# tetrad.net
KiCad netlist of a schematic drawn in EAGLE
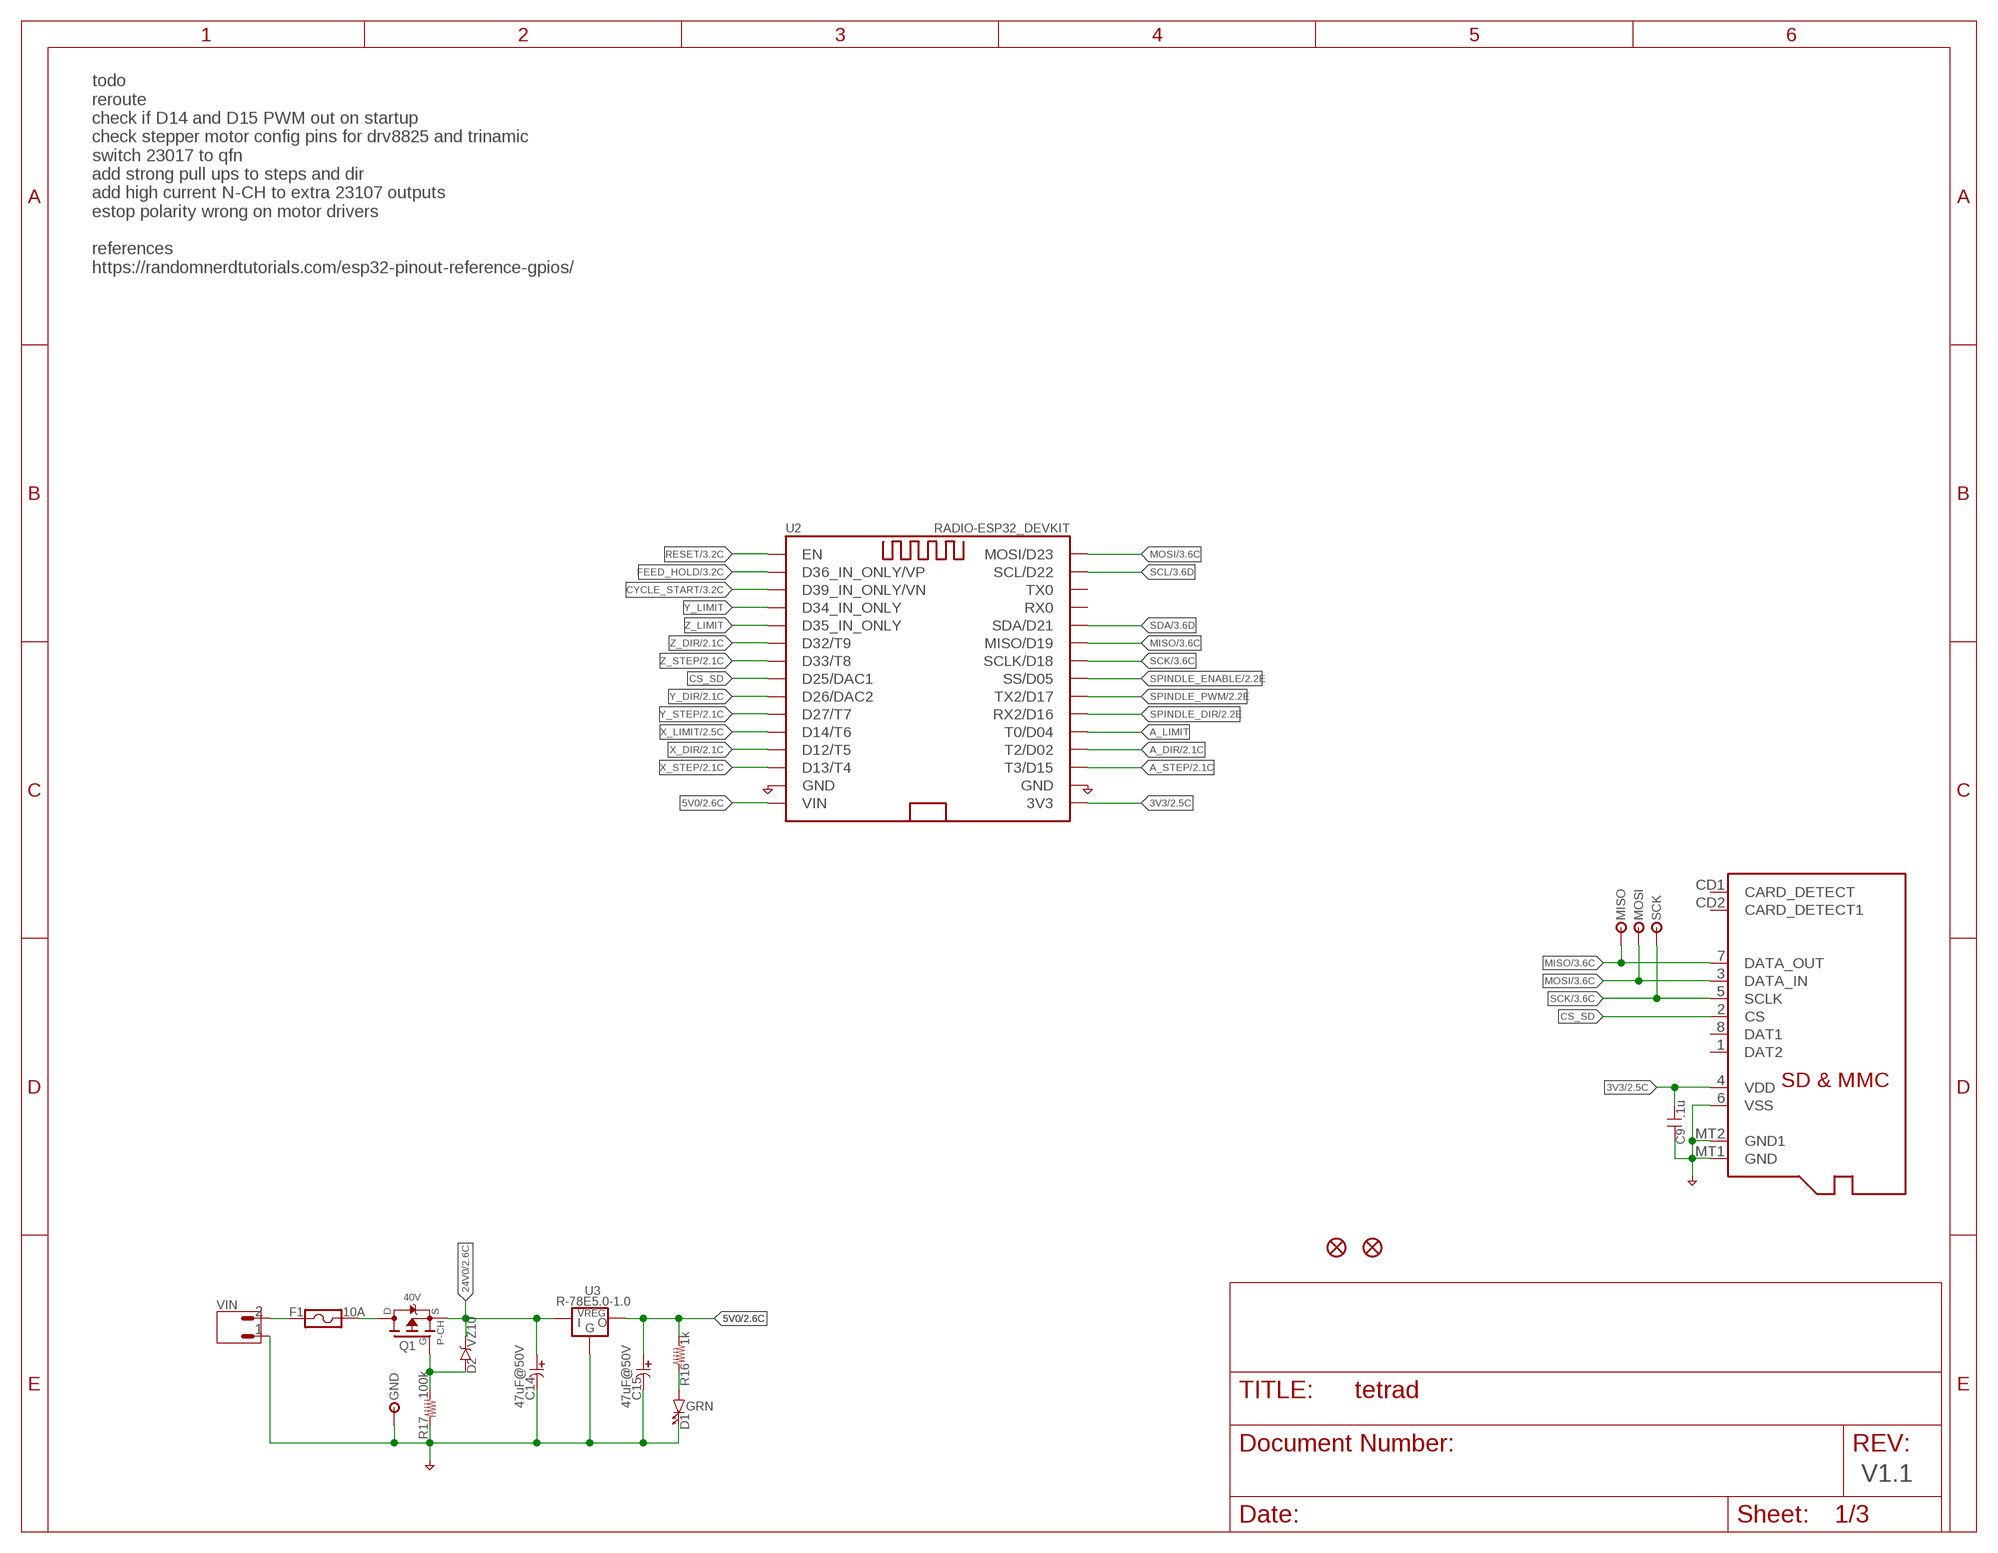
[diagram p0: schematic, sheet 1]
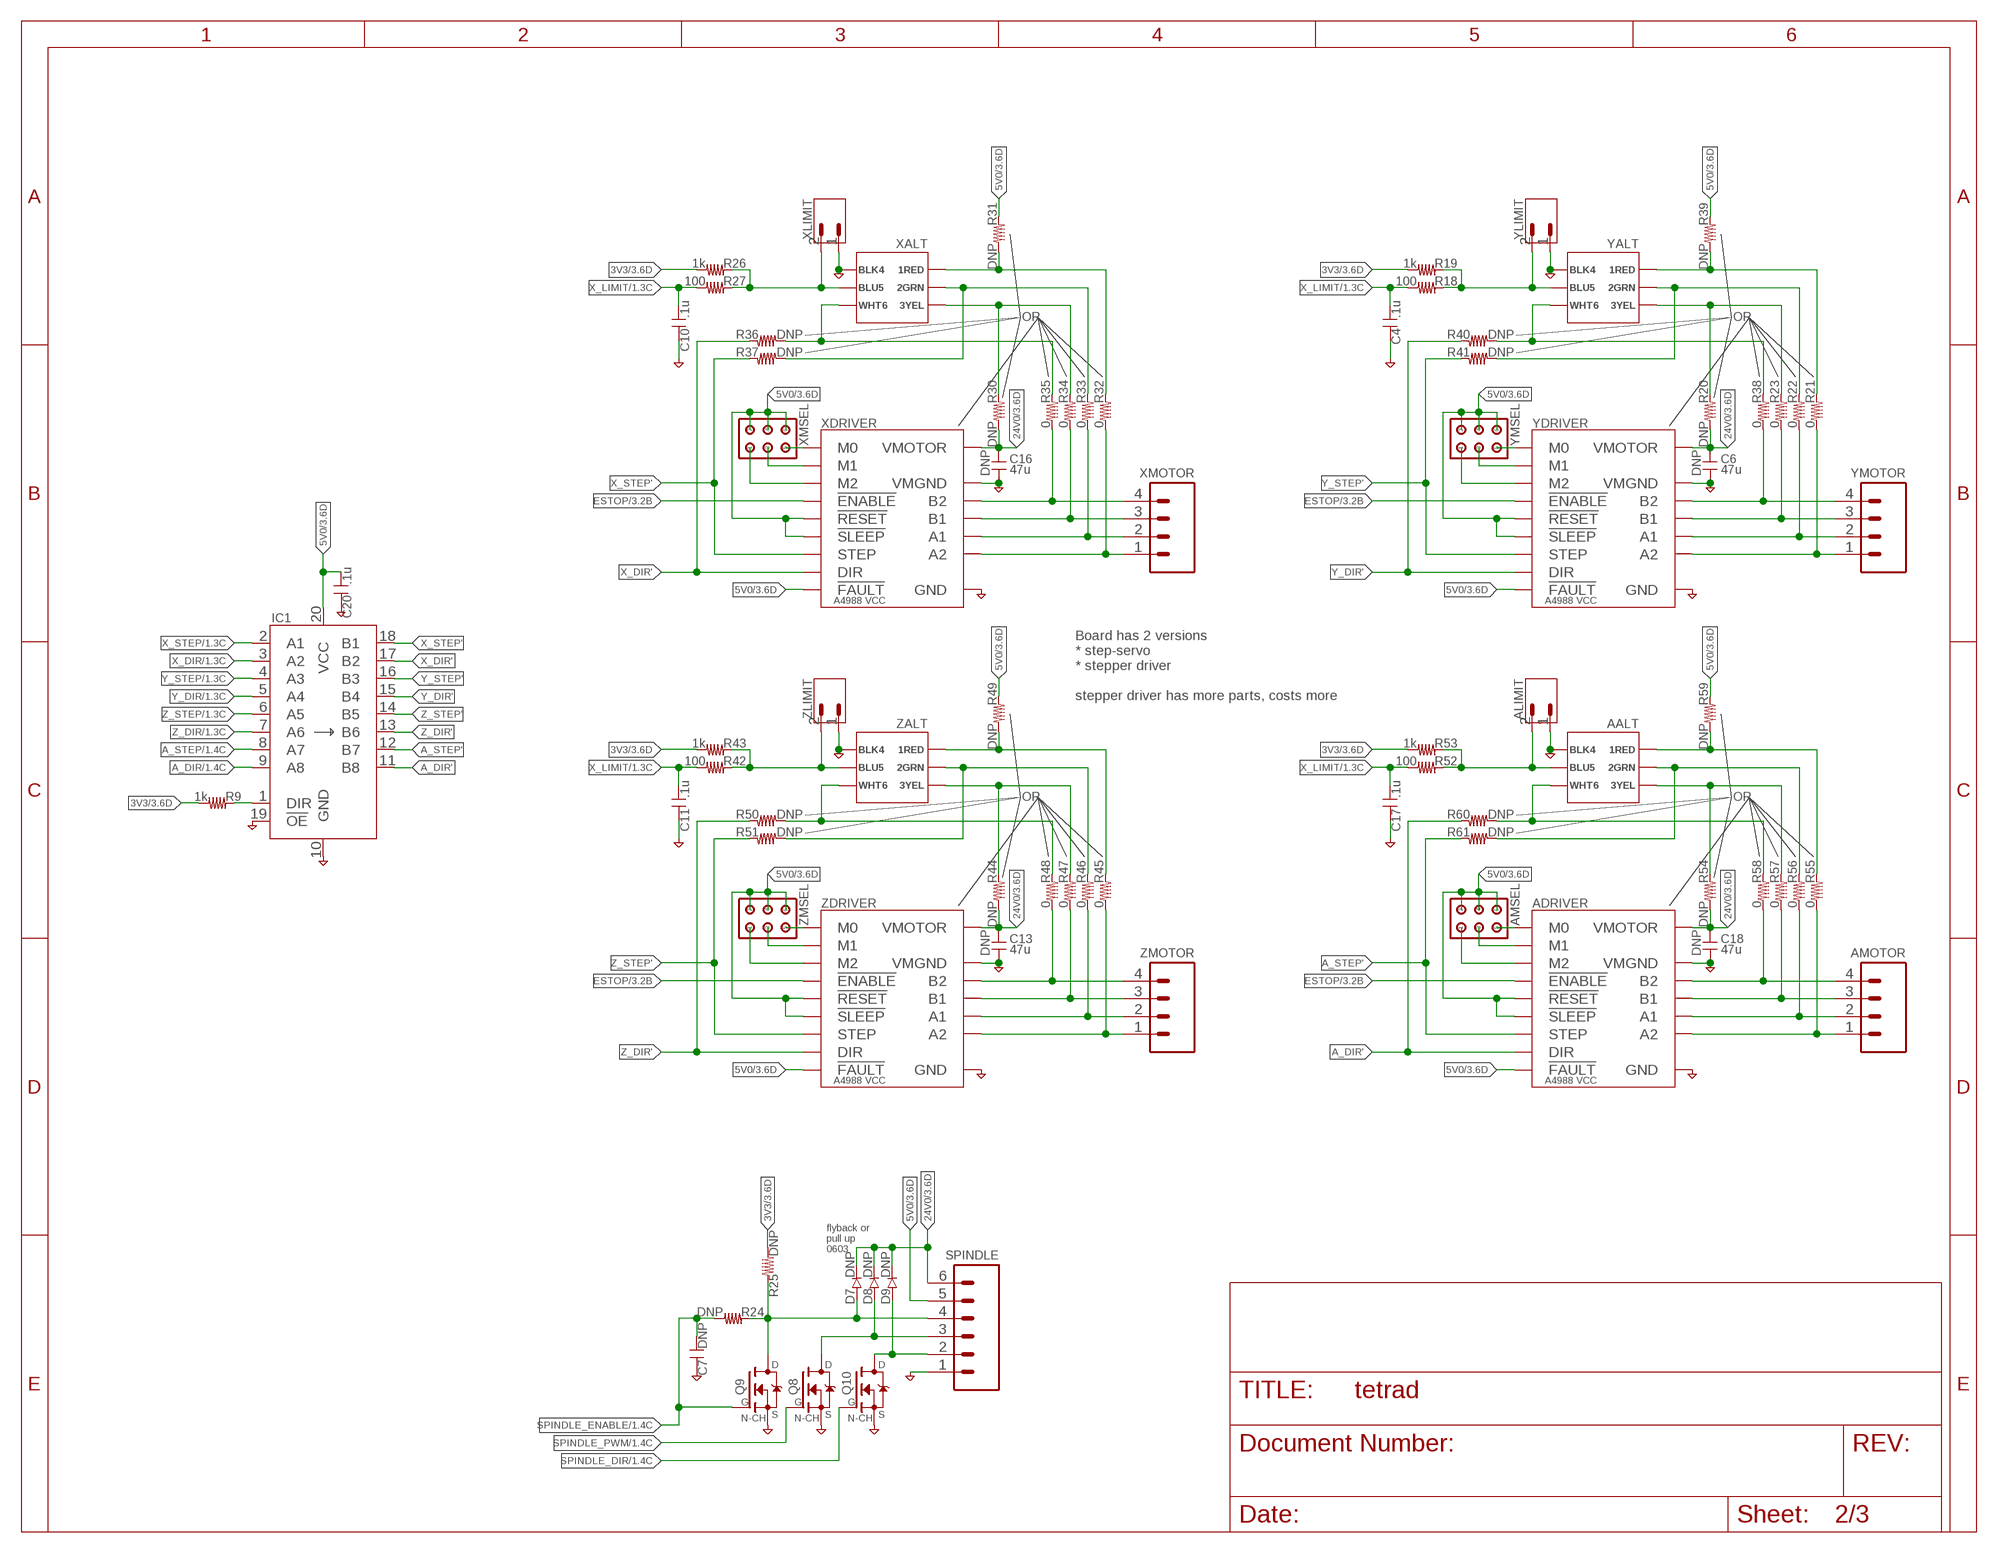
[diagram p1: schematic, sheet 2]
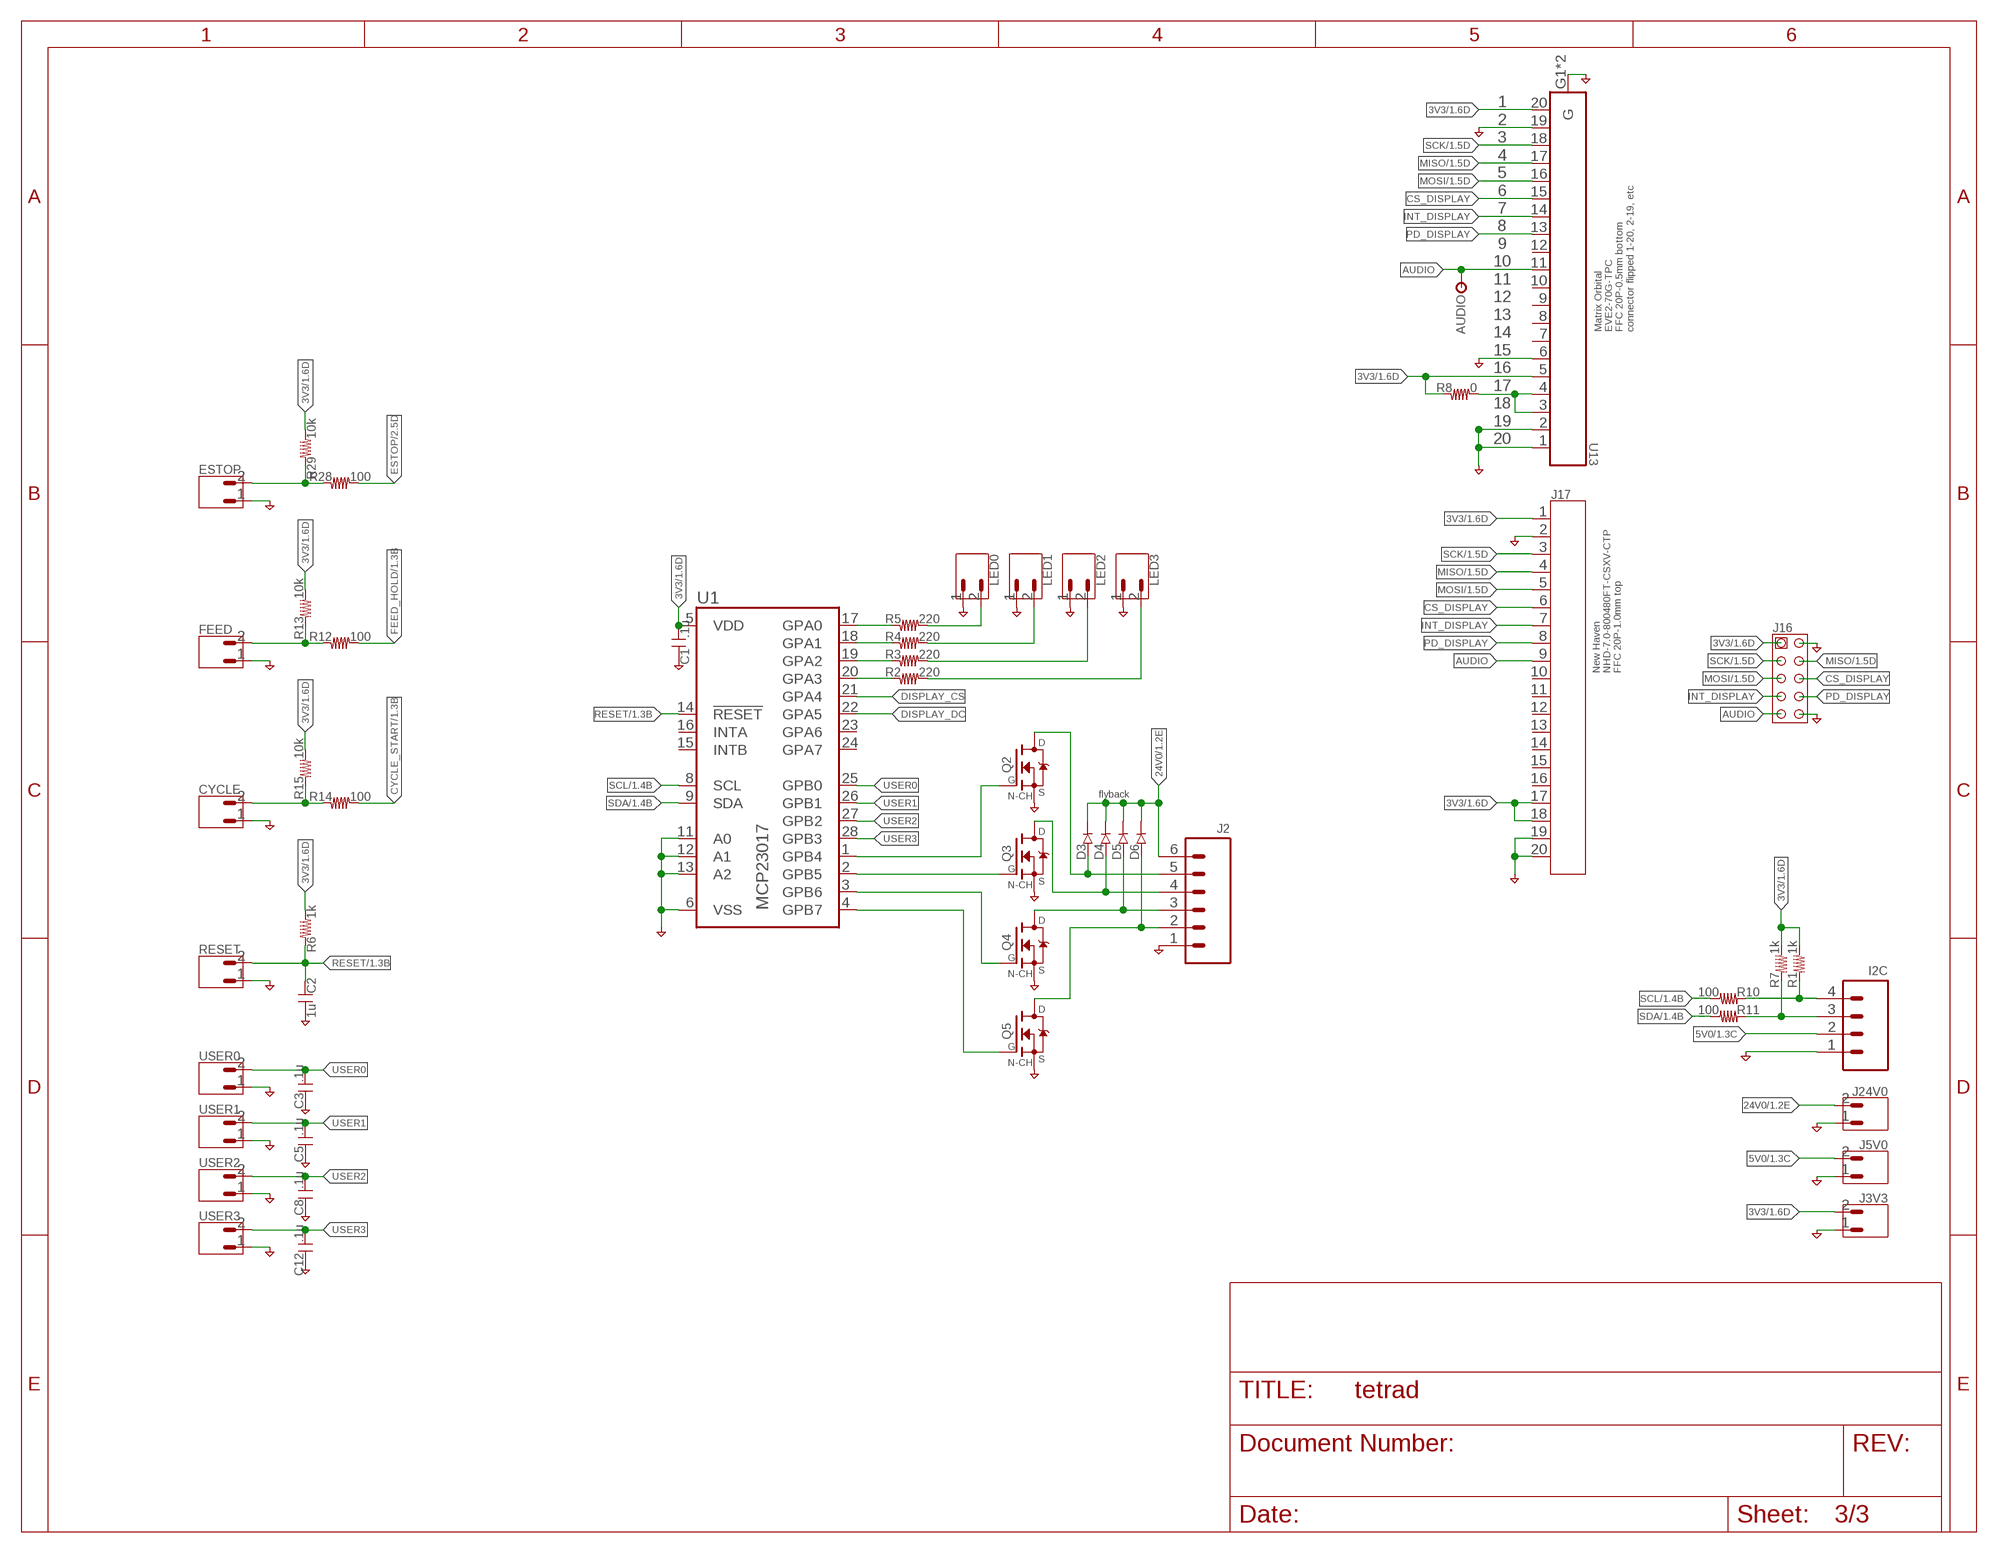
[diagram p2: schematic, sheet 3]

(export (version "E")
  (design (tool "Eeschema 10.0.6"))
  (components
    (comp (ref "AUDIO")
      (value "TESTPOINTTHRU")
      (footprint "eagle-import:TPTHRU")
      (libsource (lib "eagle-import") (part "TESTPOINTTHRU"))
    )
    (comp (ref "C1")
      (value ".1u")
      (footprint "eagle-import:C-0603")
      (libsource (lib "eagle-import") (part "C-0603"))
    )
    (comp (ref "C2")
      (value "1u")
      (footprint "eagle-import:C-0603")
      (libsource (lib "eagle-import") (part "C-0603"))
    )
    (comp (ref "C3")
      (value ".1u")
      (footprint "eagle-import:C-0603")
      (libsource (lib "eagle-import") (part "C-0603"))
    )
    (comp (ref "C5")
      (value ".1u")
      (footprint "eagle-import:C-0603")
      (libsource (lib "eagle-import") (part "C-0603"))
    )
    (comp (ref "C8")
      (value ".1u")
      (footprint "eagle-import:C-0603")
      (libsource (lib "eagle-import") (part "C-0603"))
    )
    (comp (ref "C12")
      (value ".1u")
      (footprint "eagle-import:C-0603")
      (libsource (lib "eagle-import") (part "C-0603"))
    )
    (comp (ref "CYCLE")
      (value "CONN-02-.100-VERT-HEADER")
      (footprint "eagle-import:CONN-.100-2")
      (libsource (lib "eagle-import") (part "CONN-02-.100-VERT-HEADER"))
    )
    (comp (ref "D3")
      (value "DIODE-0603-SOD523")
      (footprint "eagle-import:D-SOD523")
      (libsource (lib "eagle-import") (part "DIODE-0603-SOD523"))
    )
    (comp (ref "D4")
      (value "DIODE-0603-SOD523")
      (footprint "eagle-import:D-SOD523")
      (libsource (lib "eagle-import") (part "DIODE-0603-SOD523"))
    )
    (comp (ref "D5")
      (value "DIODE-0603-SOD523")
      (footprint "eagle-import:D-SOD523")
      (libsource (lib "eagle-import") (part "DIODE-0603-SOD523"))
    )
    (comp (ref "D6")
      (value "DIODE-0603-SOD523")
      (footprint "eagle-import:D-SOD523")
      (libsource (lib "eagle-import") (part "DIODE-0603-SOD523"))
    )
    (comp (ref "ESTOP")
      (value "CONN-02-.100-VERT-HEADER")
      (footprint "eagle-import:CONN-.100-2")
      (libsource (lib "eagle-import") (part "CONN-02-.100-VERT-HEADER"))
    )
    (comp (ref "FEED")
      (value "CONN-02-.100-VERT-HEADER")
      (footprint "eagle-import:CONN-.100-2")
      (libsource (lib "eagle-import") (part "CONN-02-.100-VERT-HEADER"))
    )
    (comp (ref "I2C")
      (value "CONN-04-.100-VERT-HEADER")
      (footprint "eagle-import:CONN-.100-4")
      (libsource (lib "eagle-import") (part "CONN-04-.100-VERT-HEADER"))
    )
    (comp (ref "J2")
      (value "CONN-06-3.81MM-PLUGIN-SCREW")
      (footprint "eagle-import:CONN-3.81MM-KF2EDG-6")
      (libsource (lib "eagle-import") (part "CONN-06-3.81MM-PLUGIN-SCREW"))
    )
    (comp (ref "J3V3")
      (value "CONN-02-.100-VERT-HEADER")
      (footprint "eagle-import:CONN-.100-2")
      (libsource (lib "eagle-import") (part "CONN-02-.100-VERT-HEADER"))
    )
    (comp (ref "J5V0")
      (value "CONN-02-.100-VERT-HEADER")
      (footprint "eagle-import:CONN-.100-2")
      (libsource (lib "eagle-import") (part "CONN-02-.100-VERT-HEADER"))
    )
    (comp (ref "J16")
      (value "CONN-05X2-SHD")
      (footprint "eagle-import:2X5-SHROUDED")
      (libsource (lib "eagle-import") (part "CONN-05X2-SHD"))
    )
    (comp (ref "J17")
      (value "CONN-20-2-84952-0")
      (footprint "eagle-import:CON20_SMT-RA_FCC-FPC2")
      (fields (field (name "MANUFACTURER_PART_NUMBER") "2849520"))
      (libsource (lib "eagle-import") (part "CONN-20-2-84952-0"))
    )
    (comp (ref "J24V0")
      (value "CONN-02-.100-VERT-HEADER")
      (footprint "eagle-import:CONN-.100-2")
      (libsource (lib "eagle-import") (part "CONN-02-.100-VERT-HEADER"))
    )
    (comp (ref "LED0")
      (value "CONN-02-.100-VERT-HEADER")
      (footprint "eagle-import:CONN-.100-2")
      (libsource (lib "eagle-import") (part "CONN-02-.100-VERT-HEADER"))
    )
    (comp (ref "LED1")
      (value "CONN-02-.100-VERT-HEADER")
      (footprint "eagle-import:CONN-.100-2")
      (libsource (lib "eagle-import") (part "CONN-02-.100-VERT-HEADER"))
    )
    (comp (ref "LED2")
      (value "CONN-02-.100-VERT-HEADER")
      (footprint "eagle-import:CONN-.100-2")
      (libsource (lib "eagle-import") (part "CONN-02-.100-VERT-HEADER"))
    )
    (comp (ref "LED3")
      (value "CONN-02-.100-VERT-HEADER")
      (footprint "eagle-import:CONN-.100-2")
      (libsource (lib "eagle-import") (part "CONN-02-.100-VERT-HEADER"))
    )
    (comp (ref "Q2")
      (value "FET-NCH-TO252")
      (footprint "eagle-import:TO252")
      (libsource (lib "eagle-import") (part "FET-NCH-TO252"))
    )
    (comp (ref "Q3")
      (value "FET-NCH-TO252")
      (footprint "eagle-import:TO252")
      (libsource (lib "eagle-import") (part "FET-NCH-TO252"))
    )
    (comp (ref "Q4")
      (value "FET-NCH-TO252")
      (footprint "eagle-import:TO252")
      (libsource (lib "eagle-import") (part "FET-NCH-TO252"))
    )
    (comp (ref "Q5")
      (value "FET-NCH-TO252")
      (footprint "eagle-import:TO252")
      (libsource (lib "eagle-import") (part "FET-NCH-TO252"))
    )
    (comp (ref "R1")
      (value "1k")
      (footprint "eagle-import:R-0603")
      (libsource (lib "eagle-import") (part "R-0603"))
    )
    (comp (ref "R2")
      (value "220")
      (footprint "eagle-import:R-0603")
      (libsource (lib "eagle-import") (part "R-0603"))
    )
    (comp (ref "R3")
      (value "220")
      (footprint "eagle-import:R-0603")
      (libsource (lib "eagle-import") (part "R-0603"))
    )
    (comp (ref "R4")
      (value "220")
      (footprint "eagle-import:R-0603")
      (libsource (lib "eagle-import") (part "R-0603"))
    )
    (comp (ref "R5")
      (value "220")
      (footprint "eagle-import:R-0603")
      (libsource (lib "eagle-import") (part "R-0603"))
    )
    (comp (ref "R6")
      (value "1k")
      (footprint "eagle-import:R-0603")
      (libsource (lib "eagle-import") (part "R-0603"))
    )
    (comp (ref "R7")
      (value "1k")
      (footprint "eagle-import:R-0603")
      (libsource (lib "eagle-import") (part "R-0603"))
    )
    (comp (ref "R8")
      (value "0")
      (footprint "eagle-import:R-0603")
      (libsource (lib "eagle-import") (part "R-0603"))
    )
    (comp (ref "R10")
      (value "100")
      (footprint "eagle-import:R-0603")
      (libsource (lib "eagle-import") (part "R-0603"))
    )
    (comp (ref "R11")
      (value "100")
      (footprint "eagle-import:R-0603")
      (libsource (lib "eagle-import") (part "R-0603"))
    )
    (comp (ref "R12")
      (value "100")
      (footprint "eagle-import:R-0603")
      (libsource (lib "eagle-import") (part "R-0603"))
    )
    (comp (ref "R13")
      (value "10k")
      (footprint "eagle-import:R-0603")
      (libsource (lib "eagle-import") (part "R-0603"))
    )
    (comp (ref "R14")
      (value "100")
      (footprint "eagle-import:R-0603")
      (libsource (lib "eagle-import") (part "R-0603"))
    )
    (comp (ref "R15")
      (value "10k")
      (footprint "eagle-import:R-0603")
      (libsource (lib "eagle-import") (part "R-0603"))
    )
    (comp (ref "R28")
      (value "100")
      (footprint "eagle-import:R-0603")
      (libsource (lib "eagle-import") (part "R-0603"))
    )
    (comp (ref "R29")
      (value "10k")
      (footprint "eagle-import:R-0603")
      (libsource (lib "eagle-import") (part "R-0603"))
    )
    (comp (ref "RESET")
      (value "CONN-02-.100-VERT-HEADER")
      (footprint "eagle-import:CONN-.100-2")
      (libsource (lib "eagle-import") (part "CONN-02-.100-VERT-HEADER"))
    )
    (comp (ref "U1")
      (value "IO-MCP23017ML")
      (footprint "eagle-import:QFN28-ML_6X6MM")
      (fields (field (name "MF") "MICROCHIP") (field (name "MPN") "MCP23017-E/ML"))
      (libsource (lib "eagle-import") (part "IO-MCP23017ML"))
    )
    (comp (ref "U13")
      (value "CONN-20-FPC-0.50MM-10051922-2010ELF")
      (footprint "eagle-import:FCI_10051922-2010ELF")
      (fields (field (name "MF") "Amphenol ICC") (field (name "MP") "10051922-2010ELF"))
      (libsource (lib "eagle-import") (part "CONN-20-FPC-0.50MM-10051922-2010ELF"))
    )
    (comp (ref "USER0")
      (value "CONN-02-.100-VERT-HEADER")
      (footprint "eagle-import:CONN-.100-2")
      (libsource (lib "eagle-import") (part "CONN-02-.100-VERT-HEADER"))
    )
    (comp (ref "USER1")
      (value "CONN-02-.100-VERT-HEADER")
      (footprint "eagle-import:CONN-.100-2")
      (libsource (lib "eagle-import") (part "CONN-02-.100-VERT-HEADER"))
    )
    (comp (ref "USER2")
      (value "CONN-02-.100-VERT-HEADER")
      (footprint "eagle-import:CONN-.100-2")
      (libsource (lib "eagle-import") (part "CONN-02-.100-VERT-HEADER"))
    )
    (comp (ref "USER3")
      (value "CONN-02-.100-VERT-HEADER")
      (footprint "eagle-import:CONN-.100-2")
      (libsource (lib "eagle-import") (part "CONN-02-.100-VERT-HEADER"))
    )
    (comp (ref "AALT")
      (value "CONN-03X2-MICROFIT-TH-SMD")
      (footprint "eagle-import:MOLEX_430450614_430450615")
      (libsource (lib "eagle-import") (part "CONN-03X2-MICROFIT-TH-SMD"))
    )
    (comp (ref "ADRIVER")
      (value "BOARD-DRV8825-CARRIER-TH-SMD")
      (footprint "eagle-import:IC_DRV8825_CARRIER_TH_SMD")
      (fields (field (name "MF") "Pololu") (field (name "MP") "DRV8825 STEPPER MOTOR DRIVER CARRIER"))
      (libsource (lib "eagle-import") (part "BOARD-DRV8825-CARRIER-TH-SMD"))
    )
    (comp (ref "ALIMIT")
      (value "CONN-02-.100-VERT-HEADER")
      (footprint "eagle-import:CONN-.100-2")
      (libsource (lib "eagle-import") (part "CONN-02-.100-VERT-HEADER"))
    )
    (comp (ref "AMOTOR")
      (value "CONN-04-.100-VERT-HEADER")
      (footprint "eagle-import:CONN-.100-4")
      (libsource (lib "eagle-import") (part "CONN-04-.100-VERT-HEADER"))
    )
    (comp (ref "AMSEL")
      (value "CONN-03X2-RH")
      (footprint "eagle-import:AMPHENOL_95278-101A06LF")
      (libsource (lib "eagle-import") (part "CONN-03X2-RH"))
    )
    (comp (ref "C4")
      (value ".1u")
      (footprint "eagle-import:C-0603")
      (libsource (lib "eagle-import") (part "C-0603"))
    )
    (comp (ref "C6")
      (value "DNP")
      (footprint "eagle-import:C-1206")
      (libsource (lib "eagle-import") (part "C-1206"))
    )
    (comp (ref "C7")
      (value "DNP")
      (footprint "eagle-import:C-0603")
      (libsource (lib "eagle-import") (part "C-0603"))
    )
    (comp (ref "C10")
      (value ".1u")
      (footprint "eagle-import:C-0603")
      (libsource (lib "eagle-import") (part "C-0603"))
    )
    (comp (ref "C11")
      (value ".1u")
      (footprint "eagle-import:C-0603")
      (libsource (lib "eagle-import") (part "C-0603"))
    )
    (comp (ref "C13")
      (value "DNP")
      (footprint "eagle-import:C-1206")
      (libsource (lib "eagle-import") (part "C-1206"))
    )
    (comp (ref "C16")
      (value "DNP")
      (footprint "eagle-import:C-1206")
      (libsource (lib "eagle-import") (part "C-1206"))
    )
    (comp (ref "C17")
      (value ".1u")
      (footprint "eagle-import:C-0603")
      (libsource (lib "eagle-import") (part "C-0603"))
    )
    (comp (ref "C18")
      (value "DNP")
      (footprint "eagle-import:C-1206")
      (libsource (lib "eagle-import") (part "C-1206"))
    )
    (comp (ref "C20")
      (value ".1u")
      (footprint "eagle-import:C-0603")
      (libsource (lib "eagle-import") (part "C-0603"))
    )
    (comp (ref "D7")
      (value "DNP")
      (footprint "eagle-import:D-SOD523")
      (libsource (lib "eagle-import") (part "DIODE-0603-SOD523"))
    )
    (comp (ref "D8")
      (value "DNP")
      (footprint "eagle-import:D-SOD523")
      (libsource (lib "eagle-import") (part "DIODE-0603-SOD523"))
    )
    (comp (ref "D9")
      (value "DNP")
      (footprint "eagle-import:D-SOD523")
      (libsource (lib "eagle-import") (part "DIODE-0603-SOD523"))
    )
    (comp (ref "IC1")
      (value "74LS245DW")
      (footprint "eagle-import:SO20W")
      (libsource (lib "eagle-import") (part "74245DWLS"))
    )
    (comp (ref "Q8")
      (value "FET-NCH-SOT23")
      (footprint "eagle-import:SOT23-3")
      (libsource (lib "eagle-import") (part "FET-NCH-SOT23"))
    )
    (comp (ref "Q9")
      (value "FET-NCH-SOT23")
      (footprint "eagle-import:SOT23-3")
      (libsource (lib "eagle-import") (part "FET-NCH-SOT23"))
    )
    (comp (ref "Q10")
      (value "FET-NCH-SOT23")
      (footprint "eagle-import:SOT23-3")
      (libsource (lib "eagle-import") (part "FET-NCH-SOT23"))
    )
    (comp (ref "R9")
      (value "1k")
      (footprint "eagle-import:R-0603")
      (libsource (lib "eagle-import") (part "R-0603"))
    )
    (comp (ref "R18")
      (value "100")
      (footprint "eagle-import:R-0603")
      (libsource (lib "eagle-import") (part "R-0603"))
    )
    (comp (ref "R19")
      (value "1k")
      (footprint "eagle-import:R-0603")
      (libsource (lib "eagle-import") (part "R-0603"))
    )
    (comp (ref "R20")
      (value "DNP")
      (footprint "eagle-import:R-0603")
      (libsource (lib "eagle-import") (part "R-0603"))
    )
    (comp (ref "R21")
      (value "0")
      (footprint "eagle-import:R-0603")
      (libsource (lib "eagle-import") (part "R-0603"))
    )
    (comp (ref "R22")
      (value "0")
      (footprint "eagle-import:R-0603")
      (libsource (lib "eagle-import") (part "R-0603"))
    )
    (comp (ref "R23")
      (value "0")
      (footprint "eagle-import:R-0603")
      (libsource (lib "eagle-import") (part "R-0603"))
    )
    (comp (ref "R24")
      (value "DNP")
      (footprint "eagle-import:R-0603")
      (libsource (lib "eagle-import") (part "R-0603"))
    )
    (comp (ref "R25")
      (value "DNP")
      (footprint "eagle-import:R-0603")
      (libsource (lib "eagle-import") (part "R-0603"))
    )
    (comp (ref "R26")
      (value "1k")
      (footprint "eagle-import:R-0603")
      (libsource (lib "eagle-import") (part "R-0603"))
    )
    (comp (ref "R27")
      (value "100")
      (footprint "eagle-import:R-0603")
      (libsource (lib "eagle-import") (part "R-0603"))
    )
    (comp (ref "R30")
      (value "DNP")
      (footprint "eagle-import:R-0603")
      (libsource (lib "eagle-import") (part "R-0603"))
    )
    (comp (ref "R31")
      (value "DNP")
      (footprint "eagle-import:R-0603")
      (libsource (lib "eagle-import") (part "R-0603"))
    )
    (comp (ref "R32")
      (value "0")
      (footprint "eagle-import:R-0603")
      (libsource (lib "eagle-import") (part "R-0603"))
    )
    (comp (ref "R33")
      (value "0")
      (footprint "eagle-import:R-0603")
      (libsource (lib "eagle-import") (part "R-0603"))
    )
    (comp (ref "R34")
      (value "0")
      (footprint "eagle-import:R-0603")
      (libsource (lib "eagle-import") (part "R-0603"))
    )
    (comp (ref "R35")
      (value "0")
      (footprint "eagle-import:R-0603")
      (libsource (lib "eagle-import") (part "R-0603"))
    )
    (comp (ref "R36")
      (value "DNP")
      (footprint "eagle-import:R-0603")
      (libsource (lib "eagle-import") (part "R-0603"))
    )
    (comp (ref "R37")
      (value "DNP")
      (footprint "eagle-import:R-0603")
      (libsource (lib "eagle-import") (part "R-0603"))
    )
    (comp (ref "R38")
      (value "0")
      (footprint "eagle-import:R-0603")
      (libsource (lib "eagle-import") (part "R-0603"))
    )
    (comp (ref "R39")
      (value "DNP")
      (footprint "eagle-import:R-0603")
      (libsource (lib "eagle-import") (part "R-0603"))
    )
    (comp (ref "R40")
      (value "DNP")
      (footprint "eagle-import:R-0603")
      (libsource (lib "eagle-import") (part "R-0603"))
    )
    (comp (ref "R41")
      (value "DNP")
      (footprint "eagle-import:R-0603")
      (libsource (lib "eagle-import") (part "R-0603"))
    )
    (comp (ref "R42")
      (value "100")
      (footprint "eagle-import:R-0603")
      (libsource (lib "eagle-import") (part "R-0603"))
    )
    (comp (ref "R43")
      (value "1k")
      (footprint "eagle-import:R-0603")
      (libsource (lib "eagle-import") (part "R-0603"))
    )
    (comp (ref "R44")
      (value "DNP")
      (footprint "eagle-import:R-0603")
      (libsource (lib "eagle-import") (part "R-0603"))
    )
    (comp (ref "R45")
      (value "0")
      (footprint "eagle-import:R-0603")
      (libsource (lib "eagle-import") (part "R-0603"))
    )
    (comp (ref "R46")
      (value "0")
      (footprint "eagle-import:R-0603")
      (libsource (lib "eagle-import") (part "R-0603"))
    )
    (comp (ref "R47")
      (value "0")
      (footprint "eagle-import:R-0603")
      (libsource (lib "eagle-import") (part "R-0603"))
    )
    (comp (ref "R48")
      (value "0")
      (footprint "eagle-import:R-0603")
      (libsource (lib "eagle-import") (part "R-0603"))
    )
    (comp (ref "R49")
      (value "DNP")
      (footprint "eagle-import:R-0603")
      (libsource (lib "eagle-import") (part "R-0603"))
    )
    (comp (ref "R50")
      (value "DNP")
      (footprint "eagle-import:R-0603")
      (libsource (lib "eagle-import") (part "R-0603"))
    )
    (comp (ref "R51")
      (value "DNP")
      (footprint "eagle-import:R-0603")
      (libsource (lib "eagle-import") (part "R-0603"))
    )
    (comp (ref "R52")
      (value "100")
      (footprint "eagle-import:R-0603")
      (libsource (lib "eagle-import") (part "R-0603"))
    )
    (comp (ref "R53")
      (value "1k")
      (footprint "eagle-import:R-0603")
      (libsource (lib "eagle-import") (part "R-0603"))
    )
    (comp (ref "R54")
      (value "DNP")
      (footprint "eagle-import:R-0603")
      (libsource (lib "eagle-import") (part "R-0603"))
    )
    (comp (ref "R55")
      (value "0")
      (footprint "eagle-import:R-0603")
      (libsource (lib "eagle-import") (part "R-0603"))
    )
    (comp (ref "R56")
      (value "0")
      (footprint "eagle-import:R-0603")
      (libsource (lib "eagle-import") (part "R-0603"))
    )
    (comp (ref "R57")
      (value "0")
      (footprint "eagle-import:R-0603")
      (libsource (lib "eagle-import") (part "R-0603"))
    )
    (comp (ref "R58")
      (value "0")
      (footprint "eagle-import:R-0603")
      (libsource (lib "eagle-import") (part "R-0603"))
    )
    (comp (ref "R59")
      (value "DNP")
      (footprint "eagle-import:R-0603")
      (libsource (lib "eagle-import") (part "R-0603"))
    )
    (comp (ref "R60")
      (value "DNP")
      (footprint "eagle-import:R-0603")
      (libsource (lib "eagle-import") (part "R-0603"))
    )
    (comp (ref "R61")
      (value "DNP")
      (footprint "eagle-import:R-0603")
      (libsource (lib "eagle-import") (part "R-0603"))
    )
    (comp (ref "SPINDLE")
      (value "CONN-06-.100-VERT-HEADER")
      (footprint "eagle-import:CONN-.100-6")
      (libsource (lib "eagle-import") (part "CONN-06-.100-VERT-HEADER"))
    )
    (comp (ref "XALT")
      (value "CONN-03X2-MICROFIT-TH-SMD")
      (footprint "eagle-import:MOLEX_430450614_430450615")
      (libsource (lib "eagle-import") (part "CONN-03X2-MICROFIT-TH-SMD"))
    )
    (comp (ref "XDRIVER")
      (value "BOARD-DRV8825-CARRIER-TH-SMD")
      (footprint "eagle-import:IC_DRV8825_CARRIER_TH_SMD")
      (fields (field (name "MF") "Pololu") (field (name "MP") "DRV8825 STEPPER MOTOR DRIVER CARRIER"))
      (libsource (lib "eagle-import") (part "BOARD-DRV8825-CARRIER-TH-SMD"))
    )
    (comp (ref "XLIMIT")
      (value "CONN-02-.100-VERT-HEADER")
      (footprint "eagle-import:CONN-.100-2")
      (libsource (lib "eagle-import") (part "CONN-02-.100-VERT-HEADER"))
    )
    (comp (ref "XMOTOR")
      (value "CONN-04-.100-VERT-HEADER")
      (footprint "eagle-import:CONN-.100-4")
      (libsource (lib "eagle-import") (part "CONN-04-.100-VERT-HEADER"))
    )
    (comp (ref "XMSEL")
      (value "CONN-03X2-RH")
      (footprint "eagle-import:AMPHENOL_95278-101A06LF")
      (libsource (lib "eagle-import") (part "CONN-03X2-RH"))
    )
    (comp (ref "YALT")
      (value "CONN-03X2-MICROFIT-TH-SMD")
      (footprint "eagle-import:MOLEX_430450614_430450615")
      (libsource (lib "eagle-import") (part "CONN-03X2-MICROFIT-TH-SMD"))
    )
    (comp (ref "YDRIVER")
      (value "BOARD-DRV8825-CARRIER-TH-SMD")
      (footprint "eagle-import:IC_DRV8825_CARRIER_TH_SMD")
      (fields (field (name "MF") "Pololu") (field (name "MP") "DRV8825 STEPPER MOTOR DRIVER CARRIER"))
      (libsource (lib "eagle-import") (part "BOARD-DRV8825-CARRIER-TH-SMD"))
    )
    (comp (ref "YLIMIT")
      (value "CONN-02-.100-VERT-HEADER")
      (footprint "eagle-import:CONN-.100-2")
      (libsource (lib "eagle-import") (part "CONN-02-.100-VERT-HEADER"))
    )
    (comp (ref "YMOTOR")
      (value "CONN-04-.100-VERT-HEADER")
      (footprint "eagle-import:CONN-.100-4")
      (libsource (lib "eagle-import") (part "CONN-04-.100-VERT-HEADER"))
    )
    (comp (ref "YMSEL")
      (value "CONN-03X2-RH")
      (footprint "eagle-import:AMPHENOL_95278-101A06LF")
      (libsource (lib "eagle-import") (part "CONN-03X2-RH"))
    )
    (comp (ref "ZALT")
      (value "CONN-03X2-MICROFIT-TH-SMD")
      (footprint "eagle-import:MOLEX_430450614_430450615")
      (libsource (lib "eagle-import") (part "CONN-03X2-MICROFIT-TH-SMD"))
    )
    (comp (ref "ZDRIVER")
      (value "BOARD-DRV8825-CARRIER-TH-SMD")
      (footprint "eagle-import:IC_DRV8825_CARRIER_TH_SMD")
      (fields (field (name "MF") "Pololu") (field (name "MP") "DRV8825 STEPPER MOTOR DRIVER CARRIER"))
      (libsource (lib "eagle-import") (part "BOARD-DRV8825-CARRIER-TH-SMD"))
    )
    (comp (ref "ZLIMIT")
      (value "CONN-02-.100-VERT-HEADER")
      (footprint "eagle-import:CONN-.100-2")
      (libsource (lib "eagle-import") (part "CONN-02-.100-VERT-HEADER"))
    )
    (comp (ref "ZMOTOR")
      (value "CONN-04-.100-VERT-HEADER")
      (footprint "eagle-import:CONN-.100-4")
      (libsource (lib "eagle-import") (part "CONN-04-.100-VERT-HEADER"))
    )
    (comp (ref "ZMSEL")
      (value "CONN-03X2-RH")
      (footprint "eagle-import:AMPHENOL_95278-101A06LF")
      (libsource (lib "eagle-import") (part "CONN-03X2-RH"))
    )
    (comp (ref "C9")
      (value ".1u")
      (footprint "eagle-import:C-0603")
      (libsource (lib "eagle-import") (part "C-0603"))
    )
    (comp (ref "C14")
      (value "47uF@50V")
      (footprint "eagle-import:C-E-6")
      (libsource (lib "eagle-import") (part "C-POLARIZED-E-6"))
    )
    (comp (ref "C15")
      (value "47uF@50V")
      (footprint "eagle-import:C-E-6")
      (libsource (lib "eagle-import") (part "C-POLARIZED-E-6"))
    )
    (comp (ref "D1")
      (value "GRN")
      (footprint "eagle-import:LED-0603")
      (libsource (lib "eagle-import") (part "LED-0603"))
    )
    (comp (ref "D2")
      (value "VZ10")
      (footprint "eagle-import:D-SOD323")
      (libsource (lib "eagle-import") (part "DIODE-ZENER-SOD323"))
    )
    (comp (ref "F1")
      (value "10A")
      (footprint "eagle-import:3557-2")
      (libsource (lib "eagle-import") (part "FUSE-HOLDER-3557-2"))
    )
    (comp (ref "FID1")
      (value "FIDUCIAL-MICRO")
      (footprint "eagle-import:FIDUCIAL-MICRO")
      (libsource (lib "eagle-import") (part "FIDUCIAL-MICRO"))
    )
    (comp (ref "FID2")
      (value "FIDUCIAL-MICRO")
      (footprint "eagle-import:FIDUCIAL-MICRO")
      (libsource (lib "eagle-import") (part "FIDUCIAL-MICRO"))
    )
    (comp (ref "GND")
      (value "TESTPOINTTHRU")
      (footprint "eagle-import:TPTHRU")
      (libsource (lib "eagle-import") (part "TESTPOINTTHRU"))
    )
    (comp (ref "J1")
      (value "CONN-MICROSD-2908-05WB-MG")
      (footprint "eagle-import:CONN-MICROSD-2908-05WB-MG")
      (libsource (lib "eagle-import") (part "CONN-MICROSD-2908-05WB-MG"))
    )
    (comp (ref "MISO")
      (value "TESTPOINTTHRU")
      (footprint "eagle-import:TPTHRU")
      (libsource (lib "eagle-import") (part "TESTPOINTTHRU"))
    )
    (comp (ref "MOSI")
      (value "TESTPOINTTHRU")
      (footprint "eagle-import:TPTHRU")
      (libsource (lib "eagle-import") (part "TESTPOINTTHRU"))
    )
    (comp (ref "Q1")
      (value "FET-PCH-TO252")
      (footprint "eagle-import:TO252")
      (libsource (lib "eagle-import") (part "FET-PCH-TO252"))
    )
    (comp (ref "R16")
      (value "1k")
      (footprint "eagle-import:R-0603")
      (libsource (lib "eagle-import") (part "R-0603"))
    )
    (comp (ref "R17")
      (value "100k")
      (footprint "eagle-import:R-0603")
      (libsource (lib "eagle-import") (part "R-0603"))
    )
    (comp (ref "SCK")
      (value "TESTPOINTTHRU")
      (footprint "eagle-import:TPTHRU")
      (libsource (lib "eagle-import") (part "TESTPOINTTHRU"))
    )
    (comp (ref "U2")
      (value "RADIO-ESP32_DEVKIT")
      (footprint "eagle-import:ESP32_DEVKIT")
      (libsource (lib "eagle-import") (part "RADIO-ESP32_DEVKIT"))
    )
    (comp (ref "U3")
      (value "R-78E5.0-1.0")
      (footprint "eagle-import:VREG-SIP3")
      (libsource (lib "eagle-import") (part "VREG-SIP3"))
    )
    (comp (ref "VIN")
      (value "CONN-02-3.81MM-PLUGIN-SCREW")
      (footprint "eagle-import:CONN-3.81MM-KF2EDG-2")
      (libsource (lib "eagle-import") (part "CONN-02-3.81MM-PLUGIN-SCREW"))
    )
  )
  (nets
    (net (code "1") (name "3V3") (class "Default")
      (node (ref "C1") (pin "1") (pinfunction "1_1") (pintype "passive"))
      (node (ref "C9") (pin "1") (pinfunction "1_1") (pintype "passive"))
      (node (ref "J1") (pin "4") (pinfunction "VDD_4") (pintype "power_in"))
      (node (ref "J16") (pin "1") (pinfunction "1_1") (pintype "passive"))
      (node (ref "J17") (pin "1") (pinfunction "1_1") (pintype "passive"))
      (node (ref "J17") (pin "17") (pinfunction "17_17") (pintype "passive"))
      (node (ref "J17") (pin "18") (pinfunction "18_18") (pintype "passive"))
      (node (ref "J3V3") (pin "2") (pinfunction "2_2") (pintype "passive"))
      (node (ref "R1") (pin "2") (pinfunction "2_2") (pintype "passive"))
      (node (ref "R13") (pin "2") (pinfunction "2_2") (pintype "passive"))
      (node (ref "R15") (pin "2") (pinfunction "2_2") (pintype "passive"))
      (node (ref "R19") (pin "2") (pinfunction "2_2") (pintype "passive"))
      (node (ref "R25") (pin "2") (pinfunction "2_2") (pintype "passive"))
      (node (ref "R26") (pin "2") (pinfunction "2_2") (pintype "passive"))
      (node (ref "R29") (pin "2") (pinfunction "2_2") (pintype "passive"))
      (node (ref "R43") (pin "2") (pinfunction "2_2") (pintype "passive"))
      (node (ref "R53") (pin "2") (pinfunction "2_2") (pintype "passive"))
      (node (ref "R6") (pin "2") (pinfunction "2_2") (pintype "passive"))
      (node (ref "R7") (pin "2") (pinfunction "2_2") (pintype "passive"))
      (node (ref "R8") (pin "1") (pinfunction "1_1") (pintype "passive"))
      (node (ref "R9") (pin "2") (pinfunction "2_2") (pintype "passive"))
      (node (ref "U1") (pin "5") (pinfunction "VDD_5") (pintype "power_in"))
      (node (ref "U13") (pin "20") (pinfunction "20_20") (pintype "bidirectional"))
      (node (ref "U13") (pin "5") (pinfunction "5_5") (pintype "passive"))
      (node (ref "U2") (pin "3V3") (pinfunction "3V3_3V3") (pintype "bidirectional"))
    )
    (net (code "2") (name "5V0") (class "Default")
      (node (ref "ADRIVER") (pin "10") (pinfunction "~{FAULT}_10") (pintype "output"))
      (node (ref "ADRIVER") (pin "10_") (pinfunction "~{FAULT}_10_") (pintype "output"))
      (node (ref "ADRIVER") (pin "5") (pinfunction "~{RESET}_5") (pintype "input"))
      (node (ref "ADRIVER") (pin "5_") (pinfunction "~{RESET}_5_") (pintype "input"))
      (node (ref "ADRIVER") (pin "6") (pinfunction "~{SLEEP}_6") (pintype "input"))
      (node (ref "ADRIVER") (pin "6_") (pinfunction "~{SLEEP}_6_") (pintype "input"))
      (node (ref "AMSEL") (pin "2") (pinfunction "2_2") (pintype "passive"))
      (node (ref "AMSEL") (pin "4") (pinfunction "4_4") (pintype "passive"))
      (node (ref "AMSEL") (pin "6") (pinfunction "6_6") (pintype "passive"))
      (node (ref "C15") (pin "+") (pinfunction "+_+") (pintype "passive"))
      (node (ref "C20") (pin "1") (pinfunction "1_1") (pintype "passive"))
      (node (ref "I2C") (pin "2") (pinfunction "2_2") (pintype "passive"))
      (node (ref "IC1") (pin "20") (pinfunction "VCC_20") (pintype "bidirectional"))
      (node (ref "J5V0") (pin "2") (pinfunction "2_2") (pintype "passive"))
      (node (ref "R16") (pin "2") (pinfunction "2_2") (pintype "passive"))
      (node (ref "R31") (pin "1") (pinfunction "1_1") (pintype "passive"))
      (node (ref "R39") (pin "1") (pinfunction "1_1") (pintype "passive"))
      (node (ref "R49") (pin "1") (pinfunction "1_1") (pintype "passive"))
      (node (ref "R59") (pin "1") (pinfunction "1_1") (pintype "passive"))
      (node (ref "SPINDLE") (pin "5") (pinfunction "5_5") (pintype "passive"))
      (node (ref "U2") (pin "VIN") (pinfunction "VIN_VIN") (pintype "bidirectional"))
      (node (ref "U3") (pin "3") (pinfunction "VOUT_3") (pintype "bidirectional"))
      (node (ref "XDRIVER") (pin "10") (pinfunction "~{FAULT}_10") (pintype "output"))
      (node (ref "XDRIVER") (pin "10_") (pinfunction "~{FAULT}_10_") (pintype "output"))
      (node (ref "XDRIVER") (pin "5") (pinfunction "~{RESET}_5") (pintype "input"))
      (node (ref "XDRIVER") (pin "5_") (pinfunction "~{RESET}_5_") (pintype "input"))
      (node (ref "XDRIVER") (pin "6") (pinfunction "~{SLEEP}_6") (pintype "input"))
      (node (ref "XDRIVER") (pin "6_") (pinfunction "~{SLEEP}_6_") (pintype "input"))
      (node (ref "XMSEL") (pin "2") (pinfunction "2_2") (pintype "passive"))
      (node (ref "XMSEL") (pin "4") (pinfunction "4_4") (pintype "passive"))
      (node (ref "XMSEL") (pin "6") (pinfunction "6_6") (pintype "passive"))
      (node (ref "YDRIVER") (pin "10") (pinfunction "~{FAULT}_10") (pintype "output"))
      (node (ref "YDRIVER") (pin "10_") (pinfunction "~{FAULT}_10_") (pintype "output"))
      (node (ref "YDRIVER") (pin "5") (pinfunction "~{RESET}_5") (pintype "input"))
      (node (ref "YDRIVER") (pin "5_") (pinfunction "~{RESET}_5_") (pintype "input"))
      (node (ref "YDRIVER") (pin "6") (pinfunction "~{SLEEP}_6") (pintype "input"))
      (node (ref "YDRIVER") (pin "6_") (pinfunction "~{SLEEP}_6_") (pintype "input"))
      (node (ref "YMSEL") (pin "2") (pinfunction "2_2") (pintype "passive"))
      (node (ref "YMSEL") (pin "4") (pinfunction "4_4") (pintype "passive"))
      (node (ref "YMSEL") (pin "6") (pinfunction "6_6") (pintype "passive"))
      (node (ref "ZDRIVER") (pin "10") (pinfunction "~{FAULT}_10") (pintype "output"))
      (node (ref "ZDRIVER") (pin "10_") (pinfunction "~{FAULT}_10_") (pintype "output"))
      (node (ref "ZDRIVER") (pin "5") (pinfunction "~{RESET}_5") (pintype "input"))
      (node (ref "ZDRIVER") (pin "5_") (pinfunction "~{RESET}_5_") (pintype "input"))
      (node (ref "ZDRIVER") (pin "6") (pinfunction "~{SLEEP}_6") (pintype "input"))
      (node (ref "ZDRIVER") (pin "6_") (pinfunction "~{SLEEP}_6_") (pintype "input"))
      (node (ref "ZMSEL") (pin "2") (pinfunction "2_2") (pintype "passive"))
      (node (ref "ZMSEL") (pin "4") (pinfunction "4_4") (pintype "passive"))
      (node (ref "ZMSEL") (pin "6") (pinfunction "6_6") (pintype "passive"))
    )
    (net (code "3") (name "24V0") (class "Default")
      (node (ref "ADRIVER") (pin "16") (pinfunction "VMOTOR_16") (pintype "power_in"))
      (node (ref "ADRIVER") (pin "16_") (pinfunction "VMOTOR_16_") (pintype "power_in"))
      (node (ref "C13") (pin "1") (pinfunction "1_1") (pintype "passive"))
      (node (ref "C14") (pin "+") (pinfunction "+_+") (pintype "passive"))
      (node (ref "C16") (pin "1") (pinfunction "1_1") (pintype "passive"))
      (node (ref "C18") (pin "1") (pinfunction "1_1") (pintype "passive"))
      (node (ref "C6") (pin "1") (pinfunction "1_1") (pintype "passive"))
      (node (ref "D2") (pin "C") (pinfunction "C_C") (pintype "passive"))
      (node (ref "D3") (pin "C") (pinfunction "C_C") (pintype "bidirectional"))
      (node (ref "D4") (pin "C") (pinfunction "C_C") (pintype "bidirectional"))
      (node (ref "D5") (pin "C") (pinfunction "C_C") (pintype "bidirectional"))
      (node (ref "D6") (pin "C") (pinfunction "C_C") (pintype "bidirectional"))
      (node (ref "D7") (pin "C") (pinfunction "C_C") (pintype "bidirectional"))
      (node (ref "D8") (pin "C") (pinfunction "C_C") (pintype "bidirectional"))
      (node (ref "D9") (pin "C") (pinfunction "C_C") (pintype "bidirectional"))
      (node (ref "J2") (pin "6") (pinfunction "6_6") (pintype "passive"))
      (node (ref "J24V0") (pin "2") (pinfunction "2_2") (pintype "passive"))
      (node (ref "Q1") (pin "2") (pinfunction "S_2") (pintype "passive"))
      (node (ref "R20") (pin "2") (pinfunction "2_2") (pintype "passive"))
      (node (ref "R30") (pin "2") (pinfunction "2_2") (pintype "passive"))
      (node (ref "R44") (pin "2") (pinfunction "2_2") (pintype "passive"))
      (node (ref "R54") (pin "2") (pinfunction "2_2") (pintype "passive"))
      (node (ref "SPINDLE") (pin "6") (pinfunction "6_6") (pintype "passive"))
      (node (ref "U3") (pin "1") (pinfunction "VIN_1") (pintype "bidirectional"))
      (node (ref "XDRIVER") (pin "16") (pinfunction "VMOTOR_16") (pintype "power_in"))
      (node (ref "XDRIVER") (pin "16_") (pinfunction "VMOTOR_16_") (pintype "power_in"))
      (node (ref "YDRIVER") (pin "16") (pinfunction "VMOTOR_16") (pintype "power_in"))
      (node (ref "YDRIVER") (pin "16_") (pinfunction "VMOTOR_16_") (pintype "power_in"))
      (node (ref "ZDRIVER") (pin "16") (pinfunction "VMOTOR_16") (pintype "power_in"))
      (node (ref "ZDRIVER") (pin "16_") (pinfunction "VMOTOR_16_") (pintype "power_in"))
    )
    (net (code "4") (name "AUDIO") (class "Default")
      (node (ref "AUDIO") (pin "1") (pinfunction "P$1_1") (pintype "bidirectional"))
      (node (ref "J16") (pin "9") (pinfunction "9_9") (pintype "passive"))
      (node (ref "J17") (pin "9") (pinfunction "9_9") (pintype "passive"))
      (node (ref "U13") (pin "11") (pinfunction "11_11") (pintype "passive"))
    )
    (net (code "5") (name "A_DIR") (class "Default")
      (node (ref "IC1") (pin "9") (pinfunction "A8_9") (pintype "bidirectional"))
      (node (ref "U2") (pin "D2") (pinfunction "T2/D02_D2") (pintype "bidirectional"))
    )
    (net (code "6") (name "A_DIR'") (class "Default")
      (node (ref "ADRIVER") (pin "8") (pinfunction "DIR_8") (pintype "input"))
      (node (ref "ADRIVER") (pin "8_") (pinfunction "DIR_8_") (pintype "input"))
      (node (ref "IC1") (pin "11") (pinfunction "B8_11") (pintype "bidirectional"))
      (node (ref "R60") (pin "1") (pinfunction "1_1") (pintype "passive"))
    )
    (net (code "7") (name "A_LIMIT") (class "Default")
      (node (ref "U2") (pin "D4") (pinfunction "T0/D04_D4") (pintype "bidirectional"))
    )
    (net (code "8") (name "A_STEP") (class "Default")
      (node (ref "IC1") (pin "8") (pinfunction "A7_8") (pintype "bidirectional"))
      (node (ref "U2") (pin "D15") (pinfunction "T3/D15_D15") (pintype "bidirectional"))
    )
    (net (code "9") (name "A_STEP'") (class "Default")
      (node (ref "ADRIVER") (pin "7") (pinfunction "STEP_7") (pintype "input"))
      (node (ref "ADRIVER") (pin "7_") (pinfunction "STEP_7_") (pintype "input"))
      (node (ref "IC1") (pin "12") (pinfunction "B7_12") (pintype "bidirectional"))
      (node (ref "R61") (pin "1") (pinfunction "1_1") (pintype "passive"))
    )
    (net (code "10") (name "CS_DISPLAY") (class "Default")
      (node (ref "J16") (pin "6") (pinfunction "6_6") (pintype "passive"))
      (node (ref "J17") (pin "6") (pinfunction "6_6") (pintype "passive"))
      (node (ref "U13") (pin "15") (pinfunction "15_15") (pintype "passive"))
    )
    (net (code "11") (name "CS_SD") (class "Default")
      (node (ref "J1") (pin "2") (pinfunction "CS_2") (pintype "input"))
      (node (ref "U2") (pin "D25") (pinfunction "D25/DAC1_D25") (pintype "bidirectional"))
    )
    (net (code "12") (name "CYCLE_START") (class "Default")
      (node (ref "R14") (pin "2") (pinfunction "2_2") (pintype "passive"))
      (node (ref "U2") (pin "VN") (pinfunction "D39_IN_ONLY/VN_VN") (pintype "bidirectional"))
    )
    (net (code "13") (name "DISPLAY_CS") (class "Default")
      (node (ref "U1") (pin "21") (pinfunction "GPA4_21") (pintype "bidirectional"))
    )
    (net (code "14") (name "DISPLAY_DC") (class "Default")
      (node (ref "U1") (pin "22") (pinfunction "GPA5_22") (pintype "bidirectional"))
    )
    (net (code "15") (name "ESTOP") (class "Default")
      (node (ref "ADRIVER") (pin "1") (pinfunction "~{ENABLE}_1") (pintype "input"))
      (node (ref "ADRIVER") (pin "1_") (pinfunction "~{ENABLE}_1_") (pintype "input"))
      (node (ref "ESTOP") (pin "2") (pinfunction "2_2") (pintype "passive"))
      (node (ref "R28") (pin "1") (pinfunction "1_1") (pintype "passive"))
      (node (ref "R29") (pin "1") (pinfunction "1_1") (pintype "passive"))
      (node (ref "XDRIVER") (pin "1") (pinfunction "~{ENABLE}_1") (pintype "input"))
      (node (ref "XDRIVER") (pin "1_") (pinfunction "~{ENABLE}_1_") (pintype "input"))
      (node (ref "YDRIVER") (pin "1") (pinfunction "~{ENABLE}_1") (pintype "input"))
      (node (ref "YDRIVER") (pin "1_") (pinfunction "~{ENABLE}_1_") (pintype "input"))
      (node (ref "ZDRIVER") (pin "1") (pinfunction "~{ENABLE}_1") (pintype "input"))
      (node (ref "ZDRIVER") (pin "1_") (pinfunction "~{ENABLE}_1_") (pintype "input"))
    )
    (net (code "16") (name "FEED_HOLD") (class "Default")
      (node (ref "R12") (pin "2") (pinfunction "2_2") (pintype "passive"))
      (node (ref "U2") (pin "VP") (pinfunction "D36_IN_ONLY/VP_VP") (pintype "bidirectional"))
    )
    (net (code "17") (name "GND") (class "Default")
      (node (ref "AALT") (pin "4") (pinfunction "4_4") (pintype "passive"))
      (node (ref "AALT") (pin "4_") (pinfunction "4_4_") (pintype "passive"))
      (node (ref "ADRIVER") (pin "15") (pinfunction "VMGND_15") (pintype "power_in"))
      (node (ref "ADRIVER") (pin "15_") (pinfunction "VMGND_15_") (pintype "power_in"))
      (node (ref "ADRIVER") (pin "9") (pinfunction "GND_9") (pintype "power_in"))
      (node (ref "ADRIVER") (pin "9_") (pinfunction "GND_9_") (pintype "power_in"))
      (node (ref "ALIMIT") (pin "1") (pinfunction "1_1") (pintype "passive"))
      (node (ref "C1") (pin "2") (pinfunction "2_2") (pintype "passive"))
      (node (ref "C10") (pin "2") (pinfunction "2_2") (pintype "passive"))
      (node (ref "C11") (pin "2") (pinfunction "2_2") (pintype "passive"))
      (node (ref "C12") (pin "2") (pinfunction "2_2") (pintype "passive"))
      (node (ref "C13") (pin "2") (pinfunction "2_2") (pintype "passive"))
      (node (ref "C14") (pin "-") (pinfunction "-_-") (pintype "passive"))
      (node (ref "C15") (pin "-") (pinfunction "-_-") (pintype "passive"))
      (node (ref "C16") (pin "2") (pinfunction "2_2") (pintype "passive"))
      (node (ref "C17") (pin "2") (pinfunction "2_2") (pintype "passive"))
      (node (ref "C18") (pin "2") (pinfunction "2_2") (pintype "passive"))
      (node (ref "C2") (pin "1") (pinfunction "1_1") (pintype "passive"))
      (node (ref "C20") (pin "2") (pinfunction "2_2") (pintype "passive"))
      (node (ref "C3") (pin "2") (pinfunction "2_2") (pintype "passive"))
      (node (ref "C4") (pin "2") (pinfunction "2_2") (pintype "passive"))
      (node (ref "C5") (pin "2") (pinfunction "2_2") (pintype "passive"))
      (node (ref "C6") (pin "2") (pinfunction "2_2") (pintype "passive"))
      (node (ref "C7") (pin "2") (pinfunction "2_2") (pintype "passive"))
      (node (ref "C8") (pin "2") (pinfunction "2_2") (pintype "passive"))
      (node (ref "C9") (pin "2") (pinfunction "2_2") (pintype "passive"))
      (node (ref "CYCLE") (pin "1") (pinfunction "1_1") (pintype "passive"))
      (node (ref "D1") (pin "C") (pinfunction "C_C") (pintype "passive"))
      (node (ref "ESTOP") (pin "1") (pinfunction "1_1") (pintype "passive"))
      (node (ref "FEED") (pin "1") (pinfunction "1_1") (pintype "passive"))
      (node (ref "GND") (pin "1") (pinfunction "P$1_1") (pintype "bidirectional"))
      (node (ref "I2C") (pin "1") (pinfunction "1_1") (pintype "passive"))
      (node (ref "IC1") (pin "10") (pinfunction "GND_10") (pintype "bidirectional"))
      (node (ref "IC1") (pin "19") (pinfunction "~{OE}_19") (pintype "input"))
      (node (ref "J1") (pin "6") (pinfunction "VSS_6") (pintype "power_in"))
      (node (ref "J1") (pin "MT1") (pinfunction "GND_MT1") (pintype "power_in"))
      (node (ref "J1") (pin "MT2") (pinfunction "GND1_MT2") (pintype "power_in"))
      (node (ref "J16") (pin "10") (pinfunction "10_10") (pintype "passive"))
      (node (ref "J16") (pin "2") (pinfunction "2_2") (pintype "passive"))
      (node (ref "J17") (pin "19") (pinfunction "19_19") (pintype "passive"))
      (node (ref "J17") (pin "2") (pinfunction "2_2") (pintype "passive"))
      (node (ref "J17") (pin "20") (pinfunction "20_20") (pintype "passive"))
      (node (ref "J2") (pin "1") (pinfunction "1_1") (pintype "passive"))
      (node (ref "J24V0") (pin "1") (pinfunction "1_1") (pintype "passive"))
      (node (ref "J3V3") (pin "1") (pinfunction "1_1") (pintype "passive"))
      (node (ref "J5V0") (pin "1") (pinfunction "1_1") (pintype "passive"))
      (node (ref "LED0") (pin "1") (pinfunction "1_1") (pintype "passive"))
      (node (ref "LED1") (pin "1") (pinfunction "1_1") (pintype "passive"))
      (node (ref "LED2") (pin "1") (pinfunction "1_1") (pintype "passive"))
      (node (ref "LED3") (pin "1") (pinfunction "1_1") (pintype "passive"))
      (node (ref "Q10") (pin "2") (pinfunction "S_2") (pintype "passive"))
      (node (ref "Q2") (pin "2") (pinfunction "S_2") (pintype "passive"))
      (node (ref "Q3") (pin "2") (pinfunction "S_2") (pintype "passive"))
      (node (ref "Q4") (pin "2") (pinfunction "S_2") (pintype "passive"))
      (node (ref "Q5") (pin "2") (pinfunction "S_2") (pintype "passive"))
      (node (ref "Q8") (pin "2") (pinfunction "S_2") (pintype "passive"))
      (node (ref "Q9") (pin "2") (pinfunction "S_2") (pintype "passive"))
      (node (ref "R17") (pin "1") (pinfunction "1_1") (pintype "passive"))
      (node (ref "RESET") (pin "1") (pinfunction "1_1") (pintype "passive"))
      (node (ref "SPINDLE") (pin "1") (pinfunction "1_1") (pintype "passive"))
      (node (ref "U1") (pin "11") (pinfunction "A0_11") (pintype "input"))
      (node (ref "U1") (pin "12") (pinfunction "A1_12") (pintype "input"))
      (node (ref "U1") (pin "13") (pinfunction "A2_13") (pintype "input"))
      (node (ref "U1") (pin "6") (pinfunction "VSS_6") (pintype "power_in"))
      (node (ref "U13") (pin "1") (pinfunction "1_1") (pintype "passive"))
      (node (ref "U13") (pin "19") (pinfunction "19_19") (pintype "bidirectional"))
      (node (ref "U13") (pin "2") (pinfunction "2_2") (pintype "passive"))
      (node (ref "U13") (pin "6") (pinfunction "6_6") (pintype "passive"))
      (node (ref "U13") (pin "G1") (pinfunction "G_G1") (pintype "bidirectional"))
      (node (ref "U13") (pin "G2") (pinfunction "G_G2") (pintype "bidirectional"))
      (node (ref "U2") (pin "GND@1") (pinfunction "GND_GND@1") (pintype "bidirectional"))
      (node (ref "U2") (pin "GND@2") (pinfunction "GND_GND@2") (pintype "bidirectional"))
      (node (ref "U3") (pin "2") (pinfunction "GND_2") (pintype "bidirectional"))
      (node (ref "USER0") (pin "1") (pinfunction "1_1") (pintype "passive"))
      (node (ref "USER1") (pin "1") (pinfunction "1_1") (pintype "passive"))
      (node (ref "USER2") (pin "1") (pinfunction "1_1") (pintype "passive"))
      (node (ref "USER3") (pin "1") (pinfunction "1_1") (pintype "passive"))
      (node (ref "VIN") (pin "1") (pinfunction "1_1") (pintype "passive"))
      (node (ref "XALT") (pin "4") (pinfunction "4_4") (pintype "passive"))
      (node (ref "XALT") (pin "4_") (pinfunction "4_4_") (pintype "passive"))
      (node (ref "XDRIVER") (pin "15") (pinfunction "VMGND_15") (pintype "power_in"))
      (node (ref "XDRIVER") (pin "15_") (pinfunction "VMGND_15_") (pintype "power_in"))
      (node (ref "XDRIVER") (pin "9") (pinfunction "GND_9") (pintype "power_in"))
      (node (ref "XDRIVER") (pin "9_") (pinfunction "GND_9_") (pintype "power_in"))
      (node (ref "XLIMIT") (pin "1") (pinfunction "1_1") (pintype "passive"))
      (node (ref "YALT") (pin "4") (pinfunction "4_4") (pintype "passive"))
      (node (ref "YALT") (pin "4_") (pinfunction "4_4_") (pintype "passive"))
      (node (ref "YDRIVER") (pin "15") (pinfunction "VMGND_15") (pintype "power_in"))
      (node (ref "YDRIVER") (pin "15_") (pinfunction "VMGND_15_") (pintype "power_in"))
      (node (ref "YDRIVER") (pin "9") (pinfunction "GND_9") (pintype "power_in"))
      (node (ref "YDRIVER") (pin "9_") (pinfunction "GND_9_") (pintype "power_in"))
      (node (ref "YLIMIT") (pin "1") (pinfunction "1_1") (pintype "passive"))
      (node (ref "ZALT") (pin "4") (pinfunction "4_4") (pintype "passive"))
      (node (ref "ZALT") (pin "4_") (pinfunction "4_4_") (pintype "passive"))
      (node (ref "ZDRIVER") (pin "15") (pinfunction "VMGND_15") (pintype "power_in"))
      (node (ref "ZDRIVER") (pin "15_") (pinfunction "VMGND_15_") (pintype "power_in"))
      (node (ref "ZDRIVER") (pin "9") (pinfunction "GND_9") (pintype "power_in"))
      (node (ref "ZDRIVER") (pin "9_") (pinfunction "GND_9_") (pintype "power_in"))
      (node (ref "ZLIMIT") (pin "1") (pinfunction "1_1") (pintype "passive"))
    )
    (net (code "18") (name "INT_DISPLAY") (class "Default")
      (node (ref "J16") (pin "7") (pinfunction "7_7") (pintype "passive"))
      (node (ref "J17") (pin "7") (pinfunction "7_7") (pintype "passive"))
      (node (ref "U13") (pin "14") (pinfunction "14_14") (pintype "passive"))
    )
    (net (code "19") (name "MISO") (class "Default")
      (node (ref "J1") (pin "7") (pinfunction "DATA_OUT_7") (pintype "output"))
      (node (ref "J16") (pin "4") (pinfunction "4_4") (pintype "passive"))
      (node (ref "J17") (pin "4") (pinfunction "4_4") (pintype "passive"))
      (node (ref "MISO") (pin "1") (pinfunction "P$1_1") (pintype "bidirectional"))
      (node (ref "U13") (pin "17") (pinfunction "17_17") (pintype "bidirectional"))
      (node (ref "U2") (pin "D19") (pinfunction "MISO/D19_D19") (pintype "bidirectional"))
    )
    (net (code "20") (name "MOSI") (class "Default")
      (node (ref "J1") (pin "3") (pinfunction "DATA_IN_3") (pintype "input"))
      (node (ref "J16") (pin "5") (pinfunction "5_5") (pintype "passive"))
      (node (ref "J17") (pin "5") (pinfunction "5_5") (pintype "passive"))
      (node (ref "MOSI") (pin "1") (pinfunction "P$1_1") (pintype "bidirectional"))
      (node (ref "U13") (pin "16") (pinfunction "16_16") (pintype "bidirectional"))
      (node (ref "U2") (pin "D23") (pinfunction "MOSI/D23_D23") (pintype "bidirectional"))
    )
    (net (code "21") (name "Net-(AALT-1-Pad1_)") (class "Default")
      (node (ref "AALT") (pin "1") (pinfunction "1_1") (pintype "passive"))
      (node (ref "AALT") (pin "1_") (pinfunction "1_1_") (pintype "passive"))
      (node (ref "R55") (pin "1") (pinfunction "1_1") (pintype "passive"))
      (node (ref "R59") (pin "2") (pinfunction "2_2") (pintype "passive"))
    )
    (net (code "22") (name "Net-(AALT-2-Pad2_)") (class "Default")
      (node (ref "AALT") (pin "2") (pinfunction "2_2") (pintype "passive"))
      (node (ref "AALT") (pin "2_") (pinfunction "2_2_") (pintype "passive"))
      (node (ref "R56") (pin "1") (pinfunction "1_1") (pintype "passive"))
      (node (ref "R61") (pin "2") (pinfunction "2_2") (pintype "passive"))
    )
    (net (code "23") (name "Net-(AALT-3-Pad3_)") (class "Default")
      (node (ref "AALT") (pin "3") (pinfunction "3_3") (pintype "passive"))
      (node (ref "AALT") (pin "3_") (pinfunction "3_3_") (pintype "passive"))
      (node (ref "R54") (pin "1") (pinfunction "1_1") (pintype "passive"))
      (node (ref "R57") (pin "1") (pinfunction "1_1") (pintype "passive"))
    )
    (net (code "24") (name "Net-(AALT-5-Pad5_)") (class "Default")
      (node (ref "AALT") (pin "5") (pinfunction "5_5") (pintype "passive"))
      (node (ref "AALT") (pin "5_") (pinfunction "5_5_") (pintype "passive"))
      (node (ref "ALIMIT") (pin "2") (pinfunction "2_2") (pintype "passive"))
      (node (ref "R52") (pin "1") (pinfunction "1_1") (pintype "passive"))
      (node (ref "R53") (pin "1") (pinfunction "1_1") (pintype "passive"))
    )
    (net (code "25") (name "Net-(AALT-6-Pad6_)") (class "Default")
      (node (ref "AALT") (pin "6") (pinfunction "6_6") (pintype "passive"))
      (node (ref "AALT") (pin "6_") (pinfunction "6_6_") (pintype "passive"))
      (node (ref "R58") (pin "1") (pinfunction "1_1") (pintype "passive"))
      (node (ref "R60") (pin "2") (pinfunction "2_2") (pintype "passive"))
    )
    (net (code "26") (name "Net-(ADRIVER-A1-Pad12)") (class "Default")
      (node (ref "ADRIVER") (pin "12") (pinfunction "A1_12") (pintype "output"))
      (node (ref "ADRIVER") (pin "12_") (pinfunction "A1_12_") (pintype "output"))
      (node (ref "AMOTOR") (pin "2") (pinfunction "2_2") (pintype "passive"))
      (node (ref "R56") (pin "2") (pinfunction "2_2") (pintype "passive"))
    )
    (net (code "27") (name "Net-(ADRIVER-A2-Pad11)") (class "Default")
      (node (ref "ADRIVER") (pin "11") (pinfunction "A2_11") (pintype "output"))
      (node (ref "ADRIVER") (pin "11_") (pinfunction "A2_11_") (pintype "output"))
      (node (ref "AMOTOR") (pin "1") (pinfunction "1_1") (pintype "passive"))
      (node (ref "R55") (pin "2") (pinfunction "2_2") (pintype "passive"))
    )
    (net (code "28") (name "Net-(ADRIVER-B1-Pad13)") (class "Default")
      (node (ref "ADRIVER") (pin "13") (pinfunction "B1_13") (pintype "output"))
      (node (ref "ADRIVER") (pin "13_") (pinfunction "B1_13_") (pintype "output"))
      (node (ref "AMOTOR") (pin "3") (pinfunction "3_3") (pintype "passive"))
      (node (ref "R57") (pin "2") (pinfunction "2_2") (pintype "passive"))
    )
    (net (code "29") (name "Net-(ADRIVER-B2-Pad14)") (class "Default")
      (node (ref "ADRIVER") (pin "14") (pinfunction "B2_14") (pintype "output"))
      (node (ref "ADRIVER") (pin "14_") (pinfunction "B2_14_") (pintype "output"))
      (node (ref "AMOTOR") (pin "4") (pinfunction "4_4") (pintype "passive"))
      (node (ref "R58") (pin "2") (pinfunction "2_2") (pintype "passive"))
    )
    (net (code "30") (name "Net-(ADRIVER-M0-Pad2)") (class "Default")
      (node (ref "ADRIVER") (pin "2") (pinfunction "M0_2") (pintype "input"))
      (node (ref "ADRIVER") (pin "2_") (pinfunction "M0_2_") (pintype "input"))
      (node (ref "AMSEL") (pin "5") (pinfunction "5_5") (pintype "passive"))
    )
    (net (code "31") (name "Net-(ADRIVER-M1-Pad3)") (class "Default")
      (node (ref "ADRIVER") (pin "3") (pinfunction "M1_3") (pintype "input"))
      (node (ref "ADRIVER") (pin "3_") (pinfunction "M1_3_") (pintype "input"))
      (node (ref "AMSEL") (pin "3") (pinfunction "3_3") (pintype "passive"))
    )
    (net (code "32") (name "Net-(ADRIVER-M2-Pad4)") (class "Default")
      (node (ref "ADRIVER") (pin "4") (pinfunction "M2_4") (pintype "input"))
      (node (ref "ADRIVER") (pin "4_") (pinfunction "M2_4_") (pintype "input"))
      (node (ref "AMSEL") (pin "1") (pinfunction "1_1") (pintype "passive"))
    )
    (net (code "33") (name "Net-(CYCLE-Pad2)") (class "Default")
      (node (ref "CYCLE") (pin "2") (pinfunction "2_2") (pintype "passive"))
      (node (ref "R14") (pin "1") (pinfunction "1_1") (pintype "passive"))
      (node (ref "R15") (pin "1") (pinfunction "1_1") (pintype "passive"))
    )
    (net (code "34") (name "Net-(D1-PadA)") (class "Default")
      (node (ref "D1") (pin "A") (pinfunction "A_A") (pintype "passive"))
      (node (ref "R16") (pin "1") (pinfunction "1_1") (pintype "passive"))
    )
    (net (code "35") (name "Net-(F1-P$1-Pad1@1)") (class "Default")
      (node (ref "F1") (pin "1@1") (pinfunction "P$1_1@1") (pintype "bidirectional"))
      (node (ref "F1") (pin "1@2") (pinfunction "P$1_1@2") (pintype "bidirectional"))
      (node (ref "VIN") (pin "2") (pinfunction "2_2") (pintype "passive"))
    )
    (net (code "36") (name "Net-(FEED-Pad2)") (class "Default")
      (node (ref "FEED") (pin "2") (pinfunction "2_2") (pintype "passive"))
      (node (ref "R12") (pin "1") (pinfunction "1_1") (pintype "passive"))
      (node (ref "R13") (pin "1") (pinfunction "1_1") (pintype "passive"))
    )
    (net (code "37") (name "Net-(I2C-Pad3)") (class "Default")
      (node (ref "I2C") (pin "3") (pinfunction "3_3") (pintype "passive"))
      (node (ref "R11") (pin "1") (pinfunction "1_1") (pintype "passive"))
      (node (ref "R7") (pin "1") (pinfunction "1_1") (pintype "passive"))
    )
    (net (code "38") (name "Net-(I2C-Pad4)") (class "Default")
      (node (ref "I2C") (pin "4") (pinfunction "4_4") (pintype "passive"))
      (node (ref "R1") (pin "1") (pinfunction "1_1") (pintype "passive"))
      (node (ref "R10") (pin "1") (pinfunction "1_1") (pintype "passive"))
    )
    (net (code "39") (name "Net-(IC1-DIR)") (class "Default")
      (node (ref "IC1") (pin "1") (pinfunction "DIR_1") (pintype "input"))
      (node (ref "R9") (pin "1") (pinfunction "1_1") (pintype "passive"))
    )
    (net (code "40") (name "Net-(LED0-Pad2)") (class "Default")
      (node (ref "LED0") (pin "2") (pinfunction "2_2") (pintype "passive"))
      (node (ref "R5") (pin "2") (pinfunction "2_2") (pintype "passive"))
    )
    (net (code "41") (name "Net-(LED1-Pad2)") (class "Default")
      (node (ref "LED1") (pin "2") (pinfunction "2_2") (pintype "passive"))
      (node (ref "R4") (pin "2") (pinfunction "2_2") (pintype "passive"))
    )
    (net (code "42") (name "Net-(LED2-Pad2)") (class "Default")
      (node (ref "LED2") (pin "2") (pinfunction "2_2") (pintype "passive"))
      (node (ref "R3") (pin "2") (pinfunction "2_2") (pintype "passive"))
    )
    (net (code "43") (name "Net-(LED3-Pad2)") (class "Default")
      (node (ref "LED3") (pin "2") (pinfunction "2_2") (pintype "passive"))
      (node (ref "R2") (pin "2") (pinfunction "2_2") (pintype "passive"))
    )
    (net (code "44") (name "Net-(Q1-D)") (class "Default")
      (node (ref "F1") (pin "2@1") (pinfunction "P$2_2@1") (pintype "bidirectional"))
      (node (ref "F1") (pin "2@2") (pinfunction "P$2_2@2") (pintype "bidirectional"))
      (node (ref "Q1") (pin "3") (pinfunction "D_3") (pintype "passive"))
    )
    (net (code "45") (name "Net-(Q1-G)") (class "Default")
      (node (ref "D2") (pin "A") (pinfunction "A_A") (pintype "passive"))
      (node (ref "Q1") (pin "1") (pinfunction "G_1") (pintype "passive"))
      (node (ref "R17") (pin "2") (pinfunction "2_2") (pintype "passive"))
    )
    (net (code "46") (name "Net-(Q2-D)") (class "Default")
      (node (ref "D3") (pin "A") (pinfunction "A_A") (pintype "bidirectional"))
      (node (ref "J2") (pin "5") (pinfunction "5_5") (pintype "passive"))
      (node (ref "Q2") (pin "3") (pinfunction "D_3") (pintype "passive"))
    )
    (net (code "47") (name "Net-(Q2-G)") (class "Default")
      (node (ref "Q2") (pin "1") (pinfunction "G_1") (pintype "passive"))
      (node (ref "U1") (pin "1") (pinfunction "GPB4_1") (pintype "bidirectional"))
    )
    (net (code "48") (name "Net-(Q3-D)") (class "Default")
      (node (ref "D4") (pin "A") (pinfunction "A_A") (pintype "bidirectional"))
      (node (ref "J2") (pin "4") (pinfunction "4_4") (pintype "passive"))
      (node (ref "Q3") (pin "3") (pinfunction "D_3") (pintype "passive"))
    )
    (net (code "49") (name "Net-(Q3-G)") (class "Default")
      (node (ref "Q3") (pin "1") (pinfunction "G_1") (pintype "passive"))
      (node (ref "U1") (pin "2") (pinfunction "GPB5_2") (pintype "bidirectional"))
    )
    (net (code "50") (name "Net-(Q4-D)") (class "Default")
      (node (ref "D5") (pin "A") (pinfunction "A_A") (pintype "bidirectional"))
      (node (ref "J2") (pin "3") (pinfunction "3_3") (pintype "passive"))
      (node (ref "Q4") (pin "3") (pinfunction "D_3") (pintype "passive"))
    )
    (net (code "51") (name "Net-(Q4-G)") (class "Default")
      (node (ref "Q4") (pin "1") (pinfunction "G_1") (pintype "passive"))
      (node (ref "U1") (pin "3") (pinfunction "GPB6_3") (pintype "bidirectional"))
    )
    (net (code "52") (name "Net-(Q5-D)") (class "Default")
      (node (ref "D6") (pin "A") (pinfunction "A_A") (pintype "bidirectional"))
      (node (ref "J2") (pin "2") (pinfunction "2_2") (pintype "passive"))
      (node (ref "Q5") (pin "3") (pinfunction "D_3") (pintype "passive"))
    )
    (net (code "53") (name "Net-(Q5-G)") (class "Default")
      (node (ref "Q5") (pin "1") (pinfunction "G_1") (pintype "passive"))
      (node (ref "U1") (pin "4") (pinfunction "GPB7_4") (pintype "bidirectional"))
    )
    (net (code "54") (name "Net-(Q8-D)") (class "Default")
      (node (ref "D8") (pin "A") (pinfunction "A_A") (pintype "bidirectional"))
      (node (ref "Q8") (pin "3") (pinfunction "D_3") (pintype "passive"))
      (node (ref "SPINDLE") (pin "3") (pinfunction "3_3") (pintype "passive"))
    )
    (net (code "55") (name "Net-(Q9-D)") (class "Default")
      (node (ref "D7") (pin "A") (pinfunction "A_A") (pintype "bidirectional"))
      (node (ref "Q9") (pin "3") (pinfunction "D_3") (pintype "passive"))
      (node (ref "R24") (pin "1") (pinfunction "1_1") (pintype "passive"))
      (node (ref "R25") (pin "1") (pinfunction "1_1") (pintype "passive"))
      (node (ref "SPINDLE") (pin "4") (pinfunction "4_4") (pintype "passive"))
    )
    (net (code "56") (name "Net-(Q10-D)") (class "Default")
      (node (ref "D9") (pin "A") (pinfunction "A_A") (pintype "bidirectional"))
      (node (ref "Q10") (pin "3") (pinfunction "D_3") (pintype "passive"))
      (node (ref "SPINDLE") (pin "2") (pinfunction "2_2") (pintype "passive"))
    )
    (net (code "57") (name "Net-(R8-Pad2)") (class "Default")
      (node (ref "R8") (pin "2") (pinfunction "2_2") (pintype "passive"))
      (node (ref "U13") (pin "3") (pinfunction "3_3") (pintype "passive"))
      (node (ref "U13") (pin "4") (pinfunction "4_4") (pintype "passive"))
    )
    (net (code "58") (name "Net-(R18-Pad1)") (class "Default")
      (node (ref "R18") (pin "1") (pinfunction "1_1") (pintype "passive"))
      (node (ref "R19") (pin "1") (pinfunction "1_1") (pintype "passive"))
      (node (ref "YALT") (pin "5") (pinfunction "5_5") (pintype "passive"))
      (node (ref "YALT") (pin "5_") (pinfunction "5_5_") (pintype "passive"))
      (node (ref "YLIMIT") (pin "2") (pinfunction "2_2") (pintype "passive"))
    )
    (net (code "59") (name "Net-(R20-Pad1)") (class "Default")
      (node (ref "R20") (pin "1") (pinfunction "1_1") (pintype "passive"))
      (node (ref "R23") (pin "1") (pinfunction "1_1") (pintype "passive"))
      (node (ref "YALT") (pin "3") (pinfunction "3_3") (pintype "passive"))
      (node (ref "YALT") (pin "3_") (pinfunction "3_3_") (pintype "passive"))
    )
    (net (code "60") (name "Net-(R21-Pad1)") (class "Default")
      (node (ref "R21") (pin "1") (pinfunction "1_1") (pintype "passive"))
      (node (ref "R39") (pin "2") (pinfunction "2_2") (pintype "passive"))
      (node (ref "YALT") (pin "1") (pinfunction "1_1") (pintype "passive"))
      (node (ref "YALT") (pin "1_") (pinfunction "1_1_") (pintype "passive"))
    )
    (net (code "61") (name "Net-(R21-Pad2)") (class "Default")
      (node (ref "R21") (pin "2") (pinfunction "2_2") (pintype "passive"))
      (node (ref "YDRIVER") (pin "11") (pinfunction "A2_11") (pintype "output"))
      (node (ref "YDRIVER") (pin "11_") (pinfunction "A2_11_") (pintype "output"))
      (node (ref "YMOTOR") (pin "1") (pinfunction "1_1") (pintype "passive"))
    )
    (net (code "62") (name "Net-(R22-Pad2)") (class "Default")
      (node (ref "R22") (pin "2") (pinfunction "2_2") (pintype "passive"))
      (node (ref "YDRIVER") (pin "12") (pinfunction "A1_12") (pintype "output"))
      (node (ref "YDRIVER") (pin "12_") (pinfunction "A1_12_") (pintype "output"))
      (node (ref "YMOTOR") (pin "2") (pinfunction "2_2") (pintype "passive"))
    )
    (net (code "63") (name "Net-(R23-Pad2)") (class "Default")
      (node (ref "R23") (pin "2") (pinfunction "2_2") (pintype "passive"))
      (node (ref "YDRIVER") (pin "13") (pinfunction "B1_13") (pintype "output"))
      (node (ref "YDRIVER") (pin "13_") (pinfunction "B1_13_") (pintype "output"))
      (node (ref "YMOTOR") (pin "3") (pinfunction "3_3") (pintype "passive"))
    )
    (net (code "64") (name "Net-(R26-Pad1)") (class "Default")
      (node (ref "R26") (pin "1") (pinfunction "1_1") (pintype "passive"))
      (node (ref "R27") (pin "1") (pinfunction "1_1") (pintype "passive"))
      (node (ref "XALT") (pin "5") (pinfunction "5_5") (pintype "passive"))
      (node (ref "XALT") (pin "5_") (pinfunction "5_5_") (pintype "passive"))
      (node (ref "XLIMIT") (pin "2") (pinfunction "2_2") (pintype "passive"))
    )
    (net (code "65") (name "Net-(R30-Pad1)") (class "Default")
      (node (ref "R30") (pin "1") (pinfunction "1_1") (pintype "passive"))
      (node (ref "R34") (pin "1") (pinfunction "1_1") (pintype "passive"))
      (node (ref "XALT") (pin "3") (pinfunction "3_3") (pintype "passive"))
      (node (ref "XALT") (pin "3_") (pinfunction "3_3_") (pintype "passive"))
    )
    (net (code "66") (name "Net-(R31-Pad2)") (class "Default")
      (node (ref "R31") (pin "2") (pinfunction "2_2") (pintype "passive"))
      (node (ref "R32") (pin "1") (pinfunction "1_1") (pintype "passive"))
      (node (ref "XALT") (pin "1") (pinfunction "1_1") (pintype "passive"))
      (node (ref "XALT") (pin "1_") (pinfunction "1_1_") (pintype "passive"))
    )
    (net (code "67") (name "Net-(R32-Pad2)") (class "Default")
      (node (ref "R32") (pin "2") (pinfunction "2_2") (pintype "passive"))
      (node (ref "XDRIVER") (pin "11") (pinfunction "A2_11") (pintype "output"))
      (node (ref "XDRIVER") (pin "11_") (pinfunction "A2_11_") (pintype "output"))
      (node (ref "XMOTOR") (pin "1") (pinfunction "1_1") (pintype "passive"))
    )
    (net (code "68") (name "Net-(R33-Pad2)") (class "Default")
      (node (ref "R33") (pin "2") (pinfunction "2_2") (pintype "passive"))
      (node (ref "XDRIVER") (pin "12") (pinfunction "A1_12") (pintype "output"))
      (node (ref "XDRIVER") (pin "12_") (pinfunction "A1_12_") (pintype "output"))
      (node (ref "XMOTOR") (pin "2") (pinfunction "2_2") (pintype "passive"))
    )
    (net (code "69") (name "Net-(R34-Pad2)") (class "Default")
      (node (ref "R34") (pin "2") (pinfunction "2_2") (pintype "passive"))
      (node (ref "XDRIVER") (pin "13") (pinfunction "B1_13") (pintype "output"))
      (node (ref "XDRIVER") (pin "13_") (pinfunction "B1_13_") (pintype "output"))
      (node (ref "XMOTOR") (pin "3") (pinfunction "3_3") (pintype "passive"))
    )
    (net (code "70") (name "Net-(R35-Pad1)") (class "Default")
      (node (ref "R35") (pin "1") (pinfunction "1_1") (pintype "passive"))
      (node (ref "R36") (pin "2") (pinfunction "2_2") (pintype "passive"))
      (node (ref "XALT") (pin "6") (pinfunction "6_6") (pintype "passive"))
      (node (ref "XALT") (pin "6_") (pinfunction "6_6_") (pintype "passive"))
    )
    (net (code "71") (name "Net-(R35-Pad2)") (class "Default")
      (node (ref "R35") (pin "2") (pinfunction "2_2") (pintype "passive"))
      (node (ref "XDRIVER") (pin "14") (pinfunction "B2_14") (pintype "output"))
      (node (ref "XDRIVER") (pin "14_") (pinfunction "B2_14_") (pintype "output"))
      (node (ref "XMOTOR") (pin "4") (pinfunction "4_4") (pintype "passive"))
    )
    (net (code "72") (name "Net-(R38-Pad1)") (class "Default")
      (node (ref "R38") (pin "1") (pinfunction "1_1") (pintype "passive"))
      (node (ref "R40") (pin "2") (pinfunction "2_2") (pintype "passive"))
      (node (ref "YALT") (pin "6") (pinfunction "6_6") (pintype "passive"))
      (node (ref "YALT") (pin "6_") (pinfunction "6_6_") (pintype "passive"))
    )
    (net (code "73") (name "Net-(R38-Pad2)") (class "Default")
      (node (ref "R38") (pin "2") (pinfunction "2_2") (pintype "passive"))
      (node (ref "YDRIVER") (pin "14") (pinfunction "B2_14") (pintype "output"))
      (node (ref "YDRIVER") (pin "14_") (pinfunction "B2_14_") (pintype "output"))
      (node (ref "YMOTOR") (pin "4") (pinfunction "4_4") (pintype "passive"))
    )
    (net (code "74") (name "Net-(R42-Pad1)") (class "Default")
      (node (ref "R42") (pin "1") (pinfunction "1_1") (pintype "passive"))
      (node (ref "R43") (pin "1") (pinfunction "1_1") (pintype "passive"))
      (node (ref "ZALT") (pin "5") (pinfunction "5_5") (pintype "passive"))
      (node (ref "ZALT") (pin "5_") (pinfunction "5_5_") (pintype "passive"))
      (node (ref "ZLIMIT") (pin "2") (pinfunction "2_2") (pintype "passive"))
    )
    (net (code "75") (name "Net-(R44-Pad1)") (class "Default")
      (node (ref "R44") (pin "1") (pinfunction "1_1") (pintype "passive"))
      (node (ref "R47") (pin "1") (pinfunction "1_1") (pintype "passive"))
      (node (ref "ZALT") (pin "3") (pinfunction "3_3") (pintype "passive"))
      (node (ref "ZALT") (pin "3_") (pinfunction "3_3_") (pintype "passive"))
    )
    (net (code "76") (name "Net-(R45-Pad1)") (class "Default")
      (node (ref "R45") (pin "1") (pinfunction "1_1") (pintype "passive"))
      (node (ref "R49") (pin "2") (pinfunction "2_2") (pintype "passive"))
      (node (ref "ZALT") (pin "1") (pinfunction "1_1") (pintype "passive"))
      (node (ref "ZALT") (pin "1_") (pinfunction "1_1_") (pintype "passive"))
    )
    (net (code "77") (name "Net-(R45-Pad2)") (class "Default")
      (node (ref "R45") (pin "2") (pinfunction "2_2") (pintype "passive"))
      (node (ref "ZDRIVER") (pin "11") (pinfunction "A2_11") (pintype "output"))
      (node (ref "ZDRIVER") (pin "11_") (pinfunction "A2_11_") (pintype "output"))
      (node (ref "ZMOTOR") (pin "1") (pinfunction "1_1") (pintype "passive"))
    )
    (net (code "78") (name "Net-(R46-Pad2)") (class "Default")
      (node (ref "R46") (pin "2") (pinfunction "2_2") (pintype "passive"))
      (node (ref "ZDRIVER") (pin "12") (pinfunction "A1_12") (pintype "output"))
      (node (ref "ZDRIVER") (pin "12_") (pinfunction "A1_12_") (pintype "output"))
      (node (ref "ZMOTOR") (pin "2") (pinfunction "2_2") (pintype "passive"))
    )
    (net (code "79") (name "Net-(R47-Pad2)") (class "Default")
      (node (ref "R47") (pin "2") (pinfunction "2_2") (pintype "passive"))
      (node (ref "ZDRIVER") (pin "13") (pinfunction "B1_13") (pintype "output"))
      (node (ref "ZDRIVER") (pin "13_") (pinfunction "B1_13_") (pintype "output"))
      (node (ref "ZMOTOR") (pin "3") (pinfunction "3_3") (pintype "passive"))
    )
    (net (code "80") (name "Net-(R48-Pad1)") (class "Default")
      (node (ref "R48") (pin "1") (pinfunction "1_1") (pintype "passive"))
      (node (ref "R50") (pin "2") (pinfunction "2_2") (pintype "passive"))
      (node (ref "ZALT") (pin "6") (pinfunction "6_6") (pintype "passive"))
      (node (ref "ZALT") (pin "6_") (pinfunction "6_6_") (pintype "passive"))
    )
    (net (code "81") (name "Net-(R48-Pad2)") (class "Default")
      (node (ref "R48") (pin "2") (pinfunction "2_2") (pintype "passive"))
      (node (ref "ZDRIVER") (pin "14") (pinfunction "B2_14") (pintype "output"))
      (node (ref "ZDRIVER") (pin "14_") (pinfunction "B2_14_") (pintype "output"))
      (node (ref "ZMOTOR") (pin "4") (pinfunction "4_4") (pintype "passive"))
    )
    (net (code "82") (name "Net-(U1-GPA0)") (class "Default")
      (node (ref "R5") (pin "1") (pinfunction "1_1") (pintype "passive"))
      (node (ref "U1") (pin "17") (pinfunction "GPA0_17") (pintype "bidirectional"))
    )
    (net (code "83") (name "Net-(U1-GPA1)") (class "Default")
      (node (ref "R4") (pin "1") (pinfunction "1_1") (pintype "passive"))
      (node (ref "U1") (pin "18") (pinfunction "GPA1_18") (pintype "bidirectional"))
    )
    (net (code "84") (name "Net-(U1-GPA2)") (class "Default")
      (node (ref "R3") (pin "1") (pinfunction "1_1") (pintype "passive"))
      (node (ref "U1") (pin "19") (pinfunction "GPA2_19") (pintype "bidirectional"))
    )
    (net (code "85") (name "Net-(U1-GPA3)") (class "Default")
      (node (ref "R2") (pin "1") (pinfunction "1_1") (pintype "passive"))
      (node (ref "U1") (pin "20") (pinfunction "GPA3_20") (pintype "bidirectional"))
    )
    (net (code "86") (name "Net-(XDRIVER-M0-Pad2)") (class "Default")
      (node (ref "XDRIVER") (pin "2") (pinfunction "M0_2") (pintype "input"))
      (node (ref "XDRIVER") (pin "2_") (pinfunction "M0_2_") (pintype "input"))
      (node (ref "XMSEL") (pin "5") (pinfunction "5_5") (pintype "passive"))
    )
    (net (code "87") (name "Net-(XDRIVER-M1-Pad3)") (class "Default")
      (node (ref "XDRIVER") (pin "3") (pinfunction "M1_3") (pintype "input"))
      (node (ref "XDRIVER") (pin "3_") (pinfunction "M1_3_") (pintype "input"))
      (node (ref "XMSEL") (pin "3") (pinfunction "3_3") (pintype "passive"))
    )
    (net (code "88") (name "Net-(XDRIVER-M2-Pad4)") (class "Default")
      (node (ref "XDRIVER") (pin "4") (pinfunction "M2_4") (pintype "input"))
      (node (ref "XDRIVER") (pin "4_") (pinfunction "M2_4_") (pintype "input"))
      (node (ref "XMSEL") (pin "1") (pinfunction "1_1") (pintype "passive"))
    )
    (net (code "89") (name "Net-(YDRIVER-M0-Pad2)") (class "Default")
      (node (ref "YDRIVER") (pin "2") (pinfunction "M0_2") (pintype "input"))
      (node (ref "YDRIVER") (pin "2_") (pinfunction "M0_2_") (pintype "input"))
      (node (ref "YMSEL") (pin "5") (pinfunction "5_5") (pintype "passive"))
    )
    (net (code "90") (name "Net-(YDRIVER-M1-Pad3)") (class "Default")
      (node (ref "YDRIVER") (pin "3") (pinfunction "M1_3") (pintype "input"))
      (node (ref "YDRIVER") (pin "3_") (pinfunction "M1_3_") (pintype "input"))
      (node (ref "YMSEL") (pin "3") (pinfunction "3_3") (pintype "passive"))
    )
    (net (code "91") (name "Net-(YDRIVER-M2-Pad4)") (class "Default")
      (node (ref "YDRIVER") (pin "4") (pinfunction "M2_4") (pintype "input"))
      (node (ref "YDRIVER") (pin "4_") (pinfunction "M2_4_") (pintype "input"))
      (node (ref "YMSEL") (pin "1") (pinfunction "1_1") (pintype "passive"))
    )
    (net (code "92") (name "Net-(ZDRIVER-M0-Pad2)") (class "Default")
      (node (ref "ZDRIVER") (pin "2") (pinfunction "M0_2") (pintype "input"))
      (node (ref "ZDRIVER") (pin "2_") (pinfunction "M0_2_") (pintype "input"))
      (node (ref "ZMSEL") (pin "5") (pinfunction "5_5") (pintype "passive"))
    )
    (net (code "93") (name "Net-(ZDRIVER-M1-Pad3)") (class "Default")
      (node (ref "ZDRIVER") (pin "3") (pinfunction "M1_3") (pintype "input"))
      (node (ref "ZDRIVER") (pin "3_") (pinfunction "M1_3_") (pintype "input"))
      (node (ref "ZMSEL") (pin "3") (pinfunction "3_3") (pintype "passive"))
    )
    (net (code "94") (name "Net-(ZDRIVER-M2-Pad4)") (class "Default")
      (node (ref "ZDRIVER") (pin "4") (pinfunction "M2_4") (pintype "input"))
      (node (ref "ZDRIVER") (pin "4_") (pinfunction "M2_4_") (pintype "input"))
      (node (ref "ZMSEL") (pin "1") (pinfunction "1_1") (pintype "passive"))
    )
    (net (code "95") (name "PD_DISPLAY") (class "Default")
      (node (ref "J16") (pin "8") (pinfunction "8_8") (pintype "passive"))
      (node (ref "J17") (pin "8") (pinfunction "8_8") (pintype "passive"))
      (node (ref "U13") (pin "13") (pinfunction "13_13") (pintype "passive"))
    )
    (net (code "96") (name "RESET") (class "Default")
      (node (ref "C2") (pin "2") (pinfunction "2_2") (pintype "passive"))
      (node (ref "R6") (pin "1") (pinfunction "1_1") (pintype "passive"))
      (node (ref "RESET") (pin "2") (pinfunction "2_2") (pintype "passive"))
      (node (ref "U1") (pin "14") (pinfunction "~{RESET}_14") (pintype "input"))
      (node (ref "U2") (pin "EN") (pinfunction "EN_EN") (pintype "bidirectional"))
    )
    (net (code "97") (name "SCK") (class "Default")
      (node (ref "J1") (pin "5") (pinfunction "SCLK_5") (pintype "input"))
      (node (ref "J16") (pin "3") (pinfunction "3_3") (pintype "passive"))
      (node (ref "J17") (pin "3") (pinfunction "3_3") (pintype "passive"))
      (node (ref "SCK") (pin "1") (pinfunction "P$1_1") (pintype "bidirectional"))
      (node (ref "U13") (pin "18") (pinfunction "18_18") (pintype "bidirectional"))
      (node (ref "U2") (pin "D18") (pinfunction "SCLK/D18_D18") (pintype "bidirectional"))
    )
    (net (code "98") (name "SCL") (class "Default")
      (node (ref "R10") (pin "2") (pinfunction "2_2") (pintype "passive"))
      (node (ref "U1") (pin "8") (pinfunction "SCL_8") (pintype "input"))
      (node (ref "U2") (pin "D22") (pinfunction "SCL/D22_D22") (pintype "bidirectional"))
    )
    (net (code "99") (name "SDA") (class "Default")
      (node (ref "R11") (pin "2") (pinfunction "2_2") (pintype "passive"))
      (node (ref "U1") (pin "9") (pinfunction "SDA_9") (pintype "bidirectional"))
      (node (ref "U2") (pin "D21") (pinfunction "SDA/D21_D21") (pintype "bidirectional"))
    )
    (net (code "100") (name "SPINDLE_DIR") (class "Default")
      (node (ref "Q10") (pin "1") (pinfunction "G_1") (pintype "passive"))
      (node (ref "U2") (pin "RX2") (pinfunction "RX2/D16_RX2") (pintype "bidirectional"))
    )
    (net (code "101") (name "SPINDLE_ENABLE") (class "Default")
      (node (ref "C7") (pin "1") (pinfunction "1_1") (pintype "passive"))
      (node (ref "Q9") (pin "1") (pinfunction "G_1") (pintype "passive"))
      (node (ref "R24") (pin "2") (pinfunction "2_2") (pintype "passive"))
      (node (ref "U2") (pin "D5") (pinfunction "SS/D05_D5") (pintype "bidirectional"))
    )
    (net (code "102") (name "SPINDLE_PWM") (class "Default")
      (node (ref "Q8") (pin "1") (pinfunction "G_1") (pintype "passive"))
      (node (ref "U2") (pin "TX2") (pinfunction "TX2/D17_TX2") (pintype "bidirectional"))
    )
    (net (code "103") (name "USER0") (class "Default")
      (node (ref "C3") (pin "1") (pinfunction "1_1") (pintype "passive"))
      (node (ref "U1") (pin "25") (pinfunction "GPB0_25") (pintype "bidirectional"))
      (node (ref "USER0") (pin "2") (pinfunction "2_2") (pintype "passive"))
    )
    (net (code "104") (name "USER1") (class "Default")
      (node (ref "C5") (pin "1") (pinfunction "1_1") (pintype "passive"))
      (node (ref "U1") (pin "26") (pinfunction "GPB1_26") (pintype "bidirectional"))
      (node (ref "USER1") (pin "2") (pinfunction "2_2") (pintype "passive"))
    )
    (net (code "105") (name "USER2") (class "Default")
      (node (ref "C8") (pin "1") (pinfunction "1_1") (pintype "passive"))
      (node (ref "U1") (pin "27") (pinfunction "GPB2_27") (pintype "bidirectional"))
      (node (ref "USER2") (pin "2") (pinfunction "2_2") (pintype "passive"))
    )
    (net (code "106") (name "USER3") (class "Default")
      (node (ref "C12") (pin "1") (pinfunction "1_1") (pintype "passive"))
      (node (ref "U1") (pin "28") (pinfunction "GPB3_28") (pintype "bidirectional"))
      (node (ref "USER3") (pin "2") (pinfunction "2_2") (pintype "passive"))
    )
    (net (code "107") (name "X_DIR") (class "Default")
      (node (ref "IC1") (pin "3") (pinfunction "A2_3") (pintype "bidirectional"))
      (node (ref "U2") (pin "D12") (pinfunction "D12/T5_D12") (pintype "bidirectional"))
    )
    (net (code "108") (name "X_DIR'") (class "Default")
      (node (ref "IC1") (pin "17") (pinfunction "B2_17") (pintype "bidirectional"))
      (node (ref "R36") (pin "1") (pinfunction "1_1") (pintype "passive"))
      (node (ref "XDRIVER") (pin "8") (pinfunction "DIR_8") (pintype "input"))
      (node (ref "XDRIVER") (pin "8_") (pinfunction "DIR_8_") (pintype "input"))
    )
    (net (code "109") (name "X_LIMIT") (class "Default")
      (node (ref "C10") (pin "1") (pinfunction "1_1") (pintype "passive"))
      (node (ref "C11") (pin "1") (pinfunction "1_1") (pintype "passive"))
      (node (ref "C17") (pin "1") (pinfunction "1_1") (pintype "passive"))
      (node (ref "C4") (pin "1") (pinfunction "1_1") (pintype "passive"))
      (node (ref "R18") (pin "2") (pinfunction "2_2") (pintype "passive"))
      (node (ref "R27") (pin "2") (pinfunction "2_2") (pintype "passive"))
      (node (ref "R42") (pin "2") (pinfunction "2_2") (pintype "passive"))
      (node (ref "R52") (pin "2") (pinfunction "2_2") (pintype "passive"))
      (node (ref "U2") (pin "D14") (pinfunction "D14/T6_D14") (pintype "bidirectional"))
    )
    (net (code "110") (name "X_STEP") (class "Default")
      (node (ref "IC1") (pin "2") (pinfunction "A1_2") (pintype "bidirectional"))
      (node (ref "U2") (pin "D13") (pinfunction "D13/T4_D13") (pintype "bidirectional"))
    )
    (net (code "111") (name "X_STEP'") (class "Default")
      (node (ref "IC1") (pin "18") (pinfunction "B1_18") (pintype "bidirectional"))
      (node (ref "R22") (pin "1") (pinfunction "1_1") (pintype "passive"))
      (node (ref "R33") (pin "1") (pinfunction "1_1") (pintype "passive"))
      (node (ref "R37") (pin "1") (pinfunction "1_1") (pintype "passive"))
      (node (ref "R37") (pin "2") (pinfunction "2_2") (pintype "passive"))
      (node (ref "R41") (pin "2") (pinfunction "2_2") (pintype "passive"))
      (node (ref "R46") (pin "1") (pinfunction "1_1") (pintype "passive"))
      (node (ref "R51") (pin "2") (pinfunction "2_2") (pintype "passive"))
      (node (ref "XALT") (pin "2") (pinfunction "2_2") (pintype "passive"))
      (node (ref "XALT") (pin "2_") (pinfunction "2_2_") (pintype "passive"))
      (node (ref "XDRIVER") (pin "7") (pinfunction "STEP_7") (pintype "input"))
      (node (ref "XDRIVER") (pin "7_") (pinfunction "STEP_7_") (pintype "input"))
      (node (ref "YALT") (pin "2") (pinfunction "2_2") (pintype "passive"))
      (node (ref "YALT") (pin "2_") (pinfunction "2_2_") (pintype "passive"))
      (node (ref "ZALT") (pin "2") (pinfunction "2_2") (pintype "passive"))
      (node (ref "ZALT") (pin "2_") (pinfunction "2_2_") (pintype "passive"))
    )
    (net (code "112") (name "Y_DIR") (class "Default")
      (node (ref "IC1") (pin "5") (pinfunction "A4_5") (pintype "bidirectional"))
      (node (ref "U2") (pin "D26") (pinfunction "D26/DAC2_D26") (pintype "bidirectional"))
    )
    (net (code "113") (name "Y_DIR'") (class "Default")
      (node (ref "IC1") (pin "15") (pinfunction "B4_15") (pintype "bidirectional"))
      (node (ref "R40") (pin "1") (pinfunction "1_1") (pintype "passive"))
      (node (ref "YDRIVER") (pin "8") (pinfunction "DIR_8") (pintype "input"))
      (node (ref "YDRIVER") (pin "8_") (pinfunction "DIR_8_") (pintype "input"))
    )
    (net (code "114") (name "Y_LIMIT") (class "Default")
      (node (ref "U2") (pin "D34") (pinfunction "D34_IN_ONLY_D34") (pintype "bidirectional"))
    )
    (net (code "115") (name "Y_STEP") (class "Default")
      (node (ref "IC1") (pin "4") (pinfunction "A3_4") (pintype "bidirectional"))
      (node (ref "U2") (pin "D27") (pinfunction "D27/T7_D27") (pintype "bidirectional"))
    )
    (net (code "116") (name "Y_STEP'") (class "Default")
      (node (ref "IC1") (pin "16") (pinfunction "B3_16") (pintype "bidirectional"))
      (node (ref "R41") (pin "1") (pinfunction "1_1") (pintype "passive"))
      (node (ref "YDRIVER") (pin "7") (pinfunction "STEP_7") (pintype "input"))
      (node (ref "YDRIVER") (pin "7_") (pinfunction "STEP_7_") (pintype "input"))
    )
    (net (code "117") (name "Z_DIR") (class "Default")
      (node (ref "IC1") (pin "7") (pinfunction "A6_7") (pintype "bidirectional"))
      (node (ref "U2") (pin "D32") (pinfunction "D32/T9_D32") (pintype "bidirectional"))
    )
    (net (code "118") (name "Z_DIR'") (class "Default")
      (node (ref "IC1") (pin "13") (pinfunction "B6_13") (pintype "bidirectional"))
      (node (ref "R50") (pin "1") (pinfunction "1_1") (pintype "passive"))
      (node (ref "ZDRIVER") (pin "8") (pinfunction "DIR_8") (pintype "input"))
      (node (ref "ZDRIVER") (pin "8_") (pinfunction "DIR_8_") (pintype "input"))
    )
    (net (code "119") (name "Z_LIMIT") (class "Default")
      (node (ref "U2") (pin "D35") (pinfunction "D35_IN_ONLY_D35") (pintype "bidirectional"))
    )
    (net (code "120") (name "Z_STEP") (class "Default")
      (node (ref "IC1") (pin "6") (pinfunction "A5_6") (pintype "bidirectional"))
      (node (ref "U2") (pin "D33") (pinfunction "D33/T8_D33") (pintype "bidirectional"))
    )
    (net (code "121") (name "Z_STEP'") (class "Default")
      (node (ref "IC1") (pin "14") (pinfunction "B5_14") (pintype "bidirectional"))
      (node (ref "R51") (pin "1") (pinfunction "1_1") (pintype "passive"))
      (node (ref "ZDRIVER") (pin "7") (pinfunction "STEP_7") (pintype "input"))
      (node (ref "ZDRIVER") (pin "7_") (pinfunction "STEP_7_") (pintype "input"))
    )
    (net (code "122") (name "unconnected-(J1-CARD_DETECT-PadCD1)") (class "Default")
      (node (ref "J1") (pin "CD1") (pinfunction "CARD_DETECT_CD1") (pintype "passive"))
    )
    (net (code "123") (name "unconnected-(J1-CARD_DETECT1-PadCD2)") (class "Default")
      (node (ref "J1") (pin "CD2") (pinfunction "CARD_DETECT1_CD2") (pintype "passive"))
    )
    (net (code "124") (name "unconnected-(J1-DAT1-Pad8)") (class "Default")
      (node (ref "J1") (pin "8") (pinfunction "DAT1_8") (pintype "bidirectional"))
    )
    (net (code "125") (name "unconnected-(J1-DAT2-Pad1)") (class "Default")
      (node (ref "J1") (pin "1") (pinfunction "DAT2_1") (pintype "bidirectional"))
    )
    (net (code "126") (name "unconnected-(J17-Pad10)") (class "Default")
      (node (ref "J17") (pin "10") (pinfunction "10_10") (pintype "passive"))
    )
    (net (code "127") (name "unconnected-(J17-Pad11)") (class "Default")
      (node (ref "J17") (pin "11") (pinfunction "11_11") (pintype "passive"))
    )
    (net (code "128") (name "unconnected-(J17-Pad12)") (class "Default")
      (node (ref "J17") (pin "12") (pinfunction "12_12") (pintype "passive"))
    )
    (net (code "129") (name "unconnected-(J17-Pad13)") (class "Default")
      (node (ref "J17") (pin "13") (pinfunction "13_13") (pintype "passive"))
    )
    (net (code "130") (name "unconnected-(J17-Pad14)") (class "Default")
      (node (ref "J17") (pin "14") (pinfunction "14_14") (pintype "passive"))
    )
    (net (code "131") (name "unconnected-(J17-Pad15)") (class "Default")
      (node (ref "J17") (pin "15") (pinfunction "15_15") (pintype "passive"))
    )
    (net (code "132") (name "unconnected-(J17-Pad16)") (class "Default")
      (node (ref "J17") (pin "16") (pinfunction "16_16") (pintype "passive"))
    )
    (net (code "133") (name "unconnected-(R28-Pad2)") (class "Default")
      (node (ref "R28") (pin "2") (pinfunction "2_2") (pintype "passive"))
    )
    (net (code "134") (name "unconnected-(U1-GPA6-Pad23)") (class "Default")
      (node (ref "U1") (pin "23") (pinfunction "GPA6_23") (pintype "bidirectional"))
    )
    (net (code "135") (name "unconnected-(U1-GPA7-Pad24)") (class "Default")
      (node (ref "U1") (pin "24") (pinfunction "GPA7_24") (pintype "bidirectional"))
    )
    (net (code "136") (name "unconnected-(U1-INTA-Pad16)") (class "Default")
      (node (ref "U1") (pin "16") (pinfunction "INTA_16") (pintype "output"))
    )
    (net (code "137") (name "unconnected-(U1-INTB-Pad15)") (class "Default")
      (node (ref "U1") (pin "15") (pinfunction "INTB_15") (pintype "output"))
    )
    (net (code "138") (name "unconnected-(U2-PadRX0)") (class "Default")
      (node (ref "U2") (pin "RX0") (pinfunction "RX0_RX0") (pintype "bidirectional"))
    )
    (net (code "139") (name "unconnected-(U2-PadTX0)") (class "Default")
      (node (ref "U2") (pin "TX0") (pinfunction "TX0_TX0") (pintype "bidirectional"))
    )
    (net (code "140") (name "unconnected-(U13-Pad7)") (class "Default")
      (node (ref "U13") (pin "7") (pinfunction "7_7") (pintype "passive"))
    )
    (net (code "141") (name "unconnected-(U13-Pad8)") (class "Default")
      (node (ref "U13") (pin "8") (pinfunction "8_8") (pintype "passive"))
    )
    (net (code "142") (name "unconnected-(U13-Pad9)") (class "Default")
      (node (ref "U13") (pin "9") (pinfunction "9_9") (pintype "passive"))
    )
    (net (code "143") (name "unconnected-(U13-Pad10)") (class "Default")
      (node (ref "U13") (pin "10") (pinfunction "10_10") (pintype "passive"))
    )
    (net (code "144") (name "unconnected-(U13-Pad12)") (class "Default")
      (node (ref "U13") (pin "12") (pinfunction "12_12") (pintype "passive"))
    )
  )
)
